# XMICRO-BP8.net
KiCad netlist of a schematic drawn in EAGLE
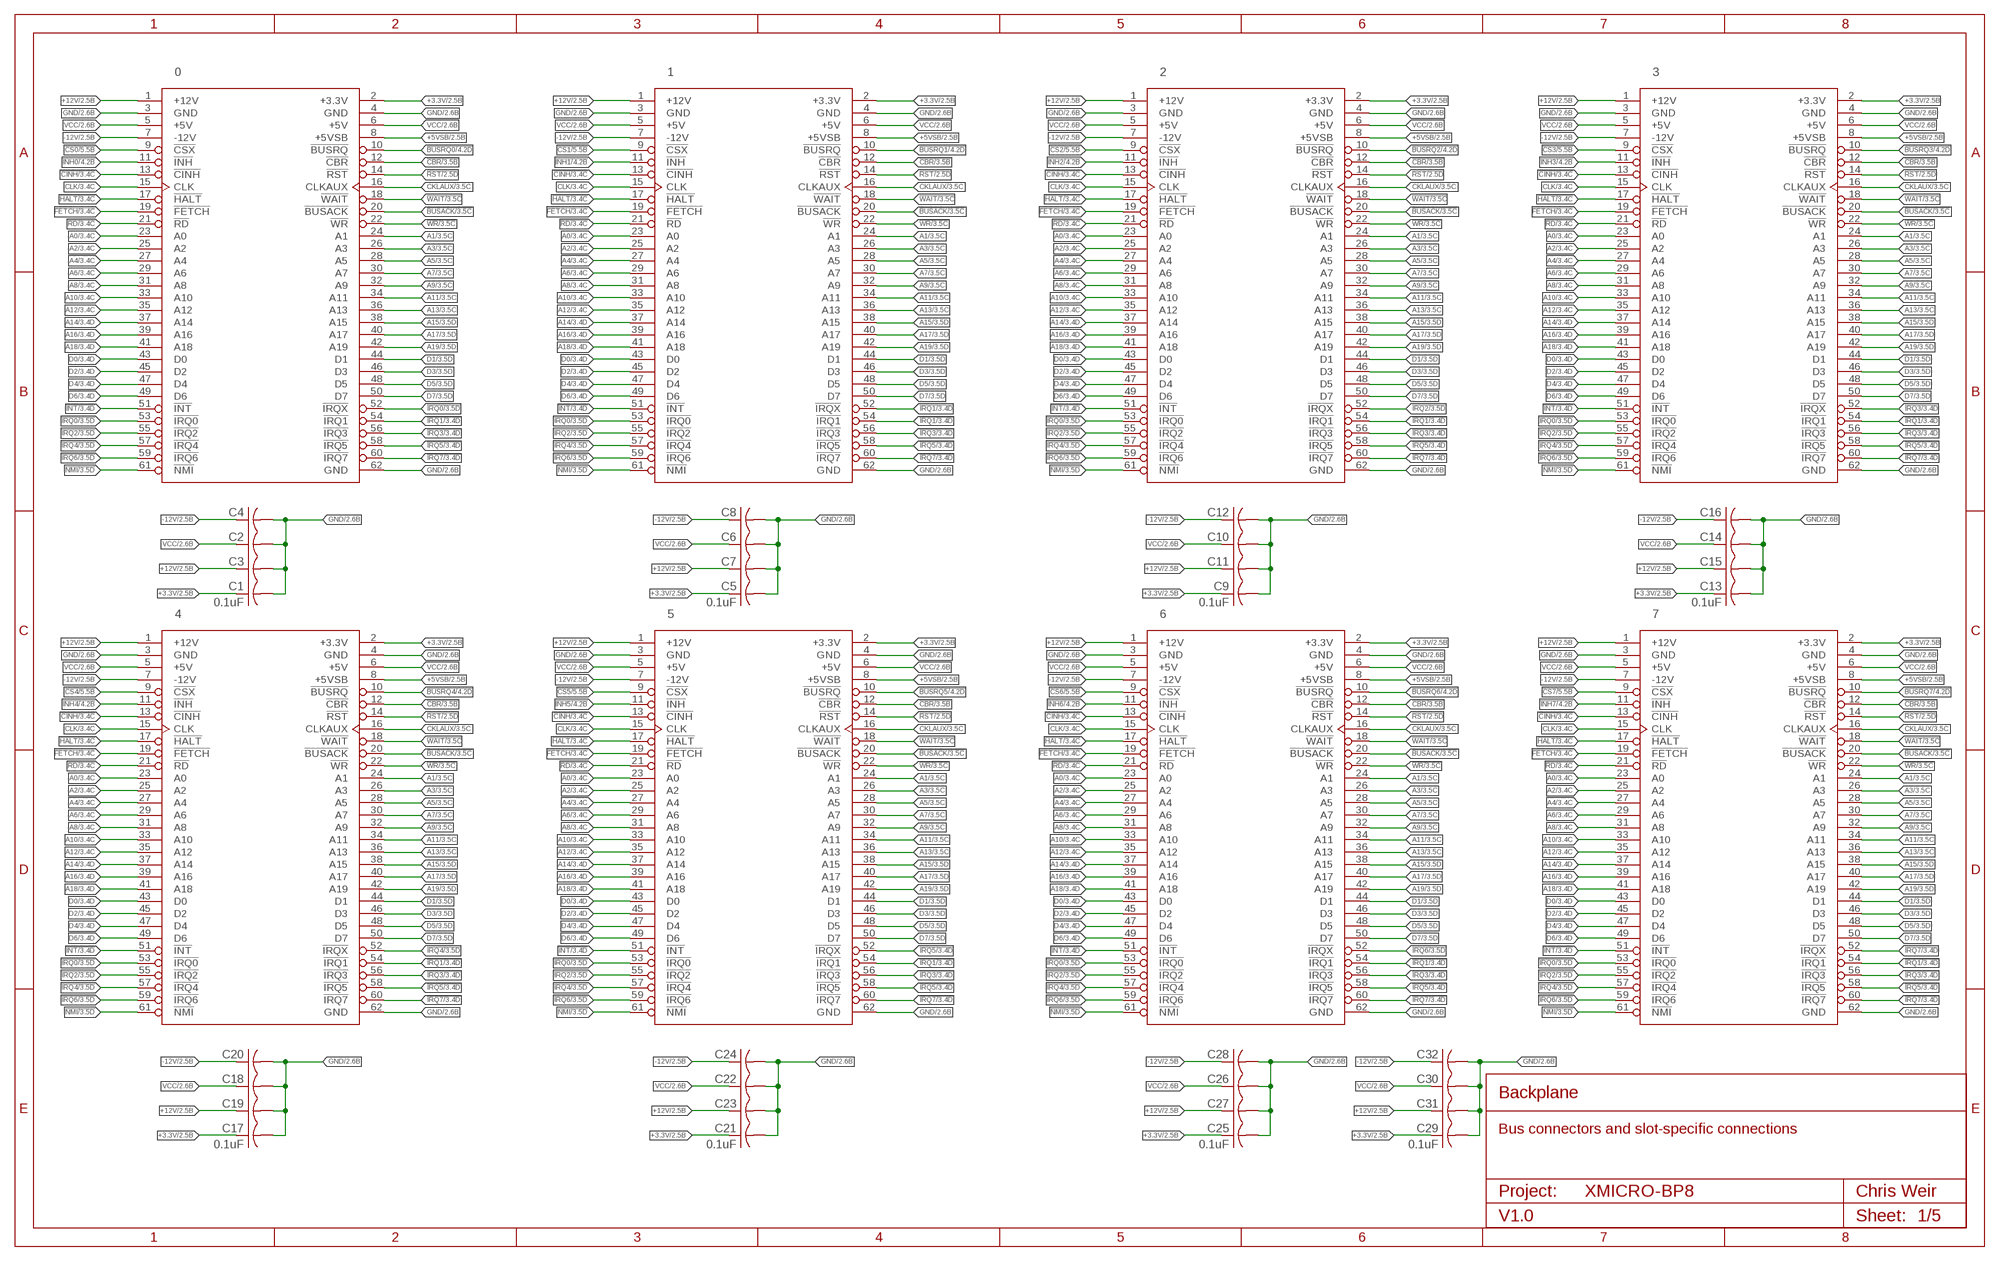
[diagram p0: schematic, sheet 1]
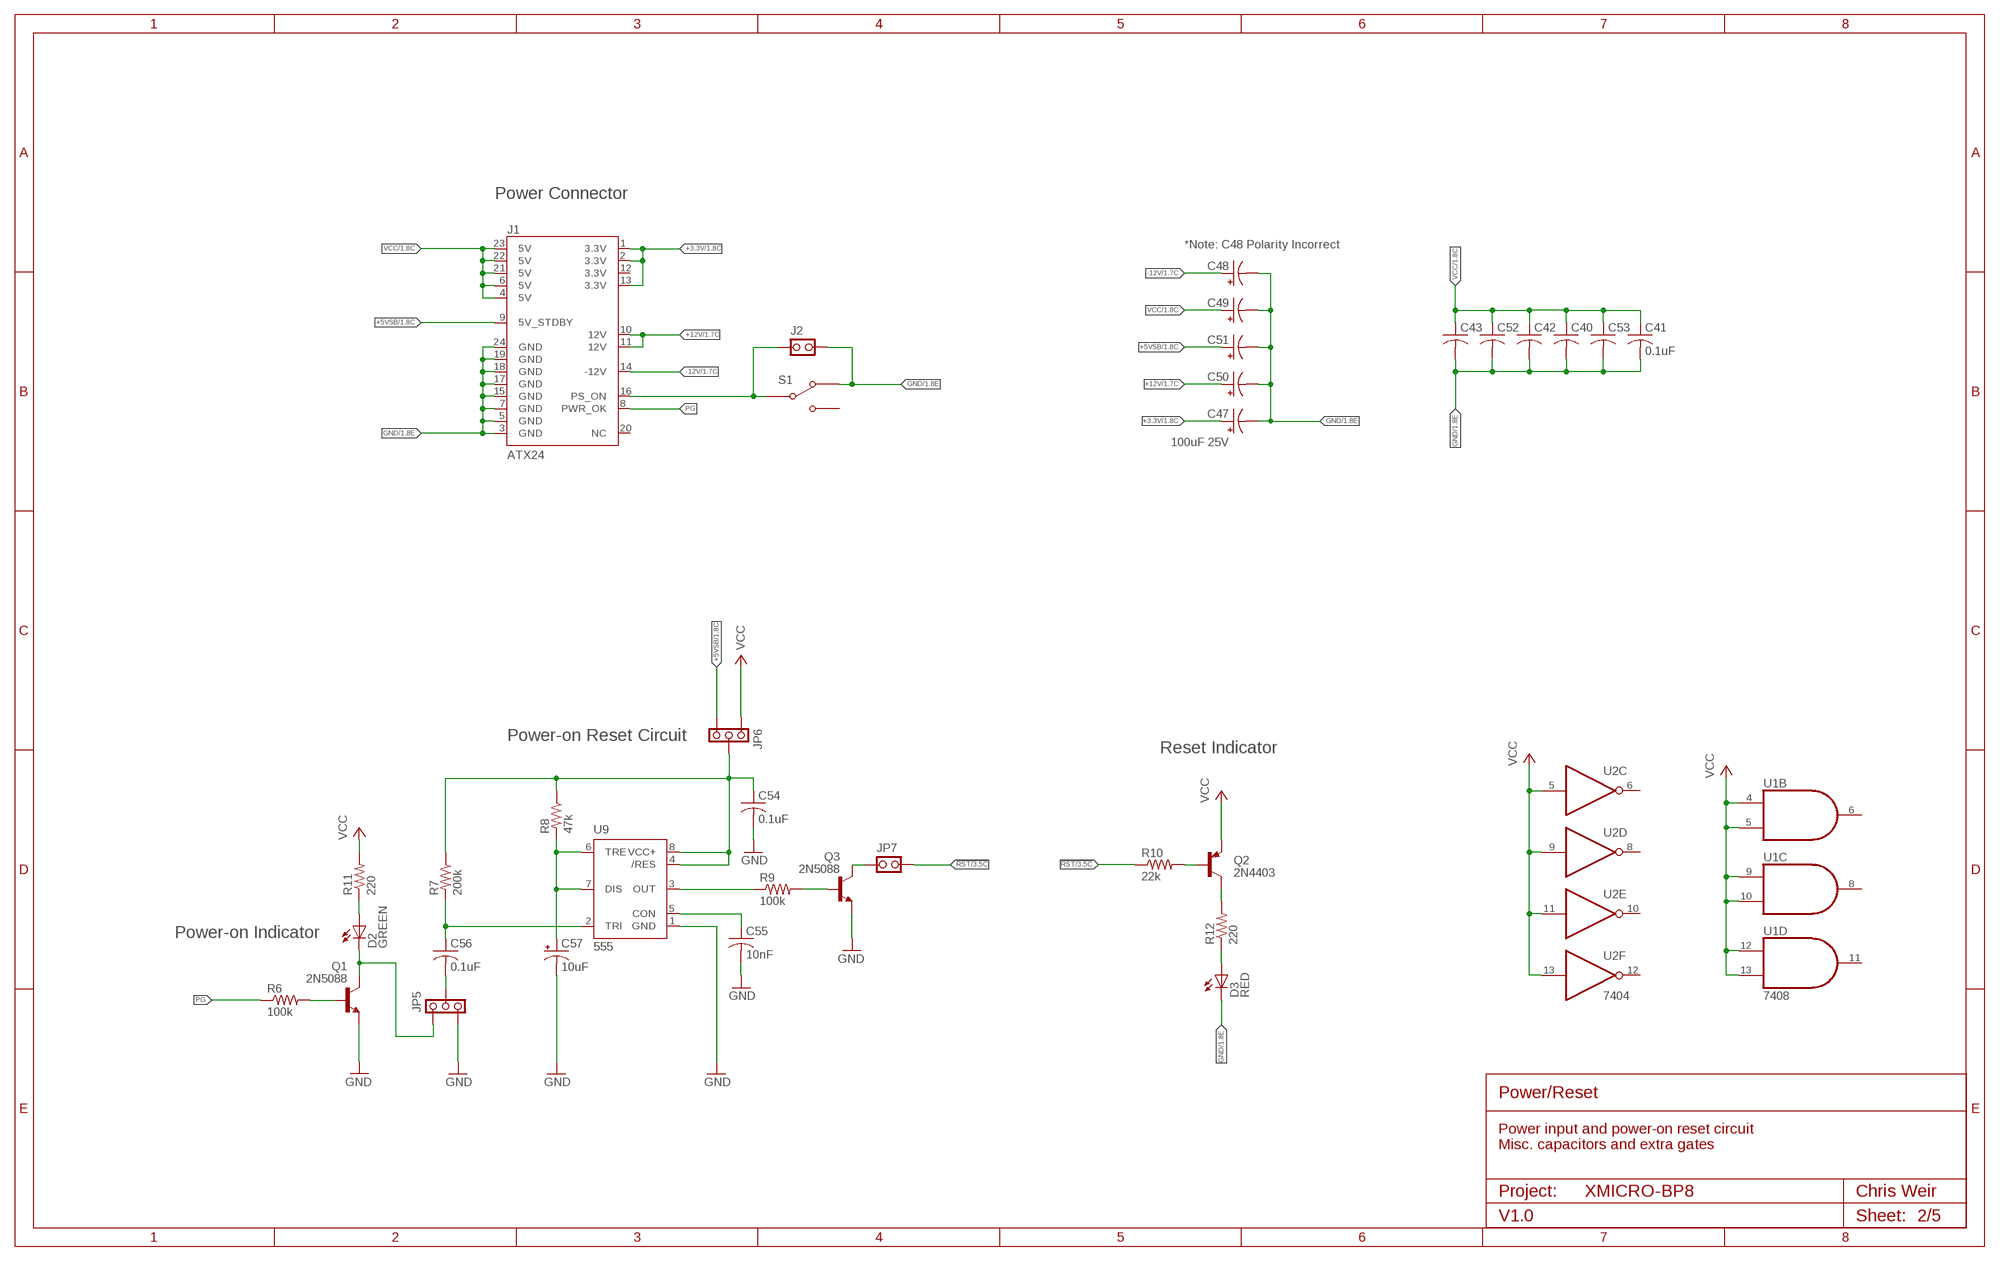
[diagram p1: schematic, sheet 2]
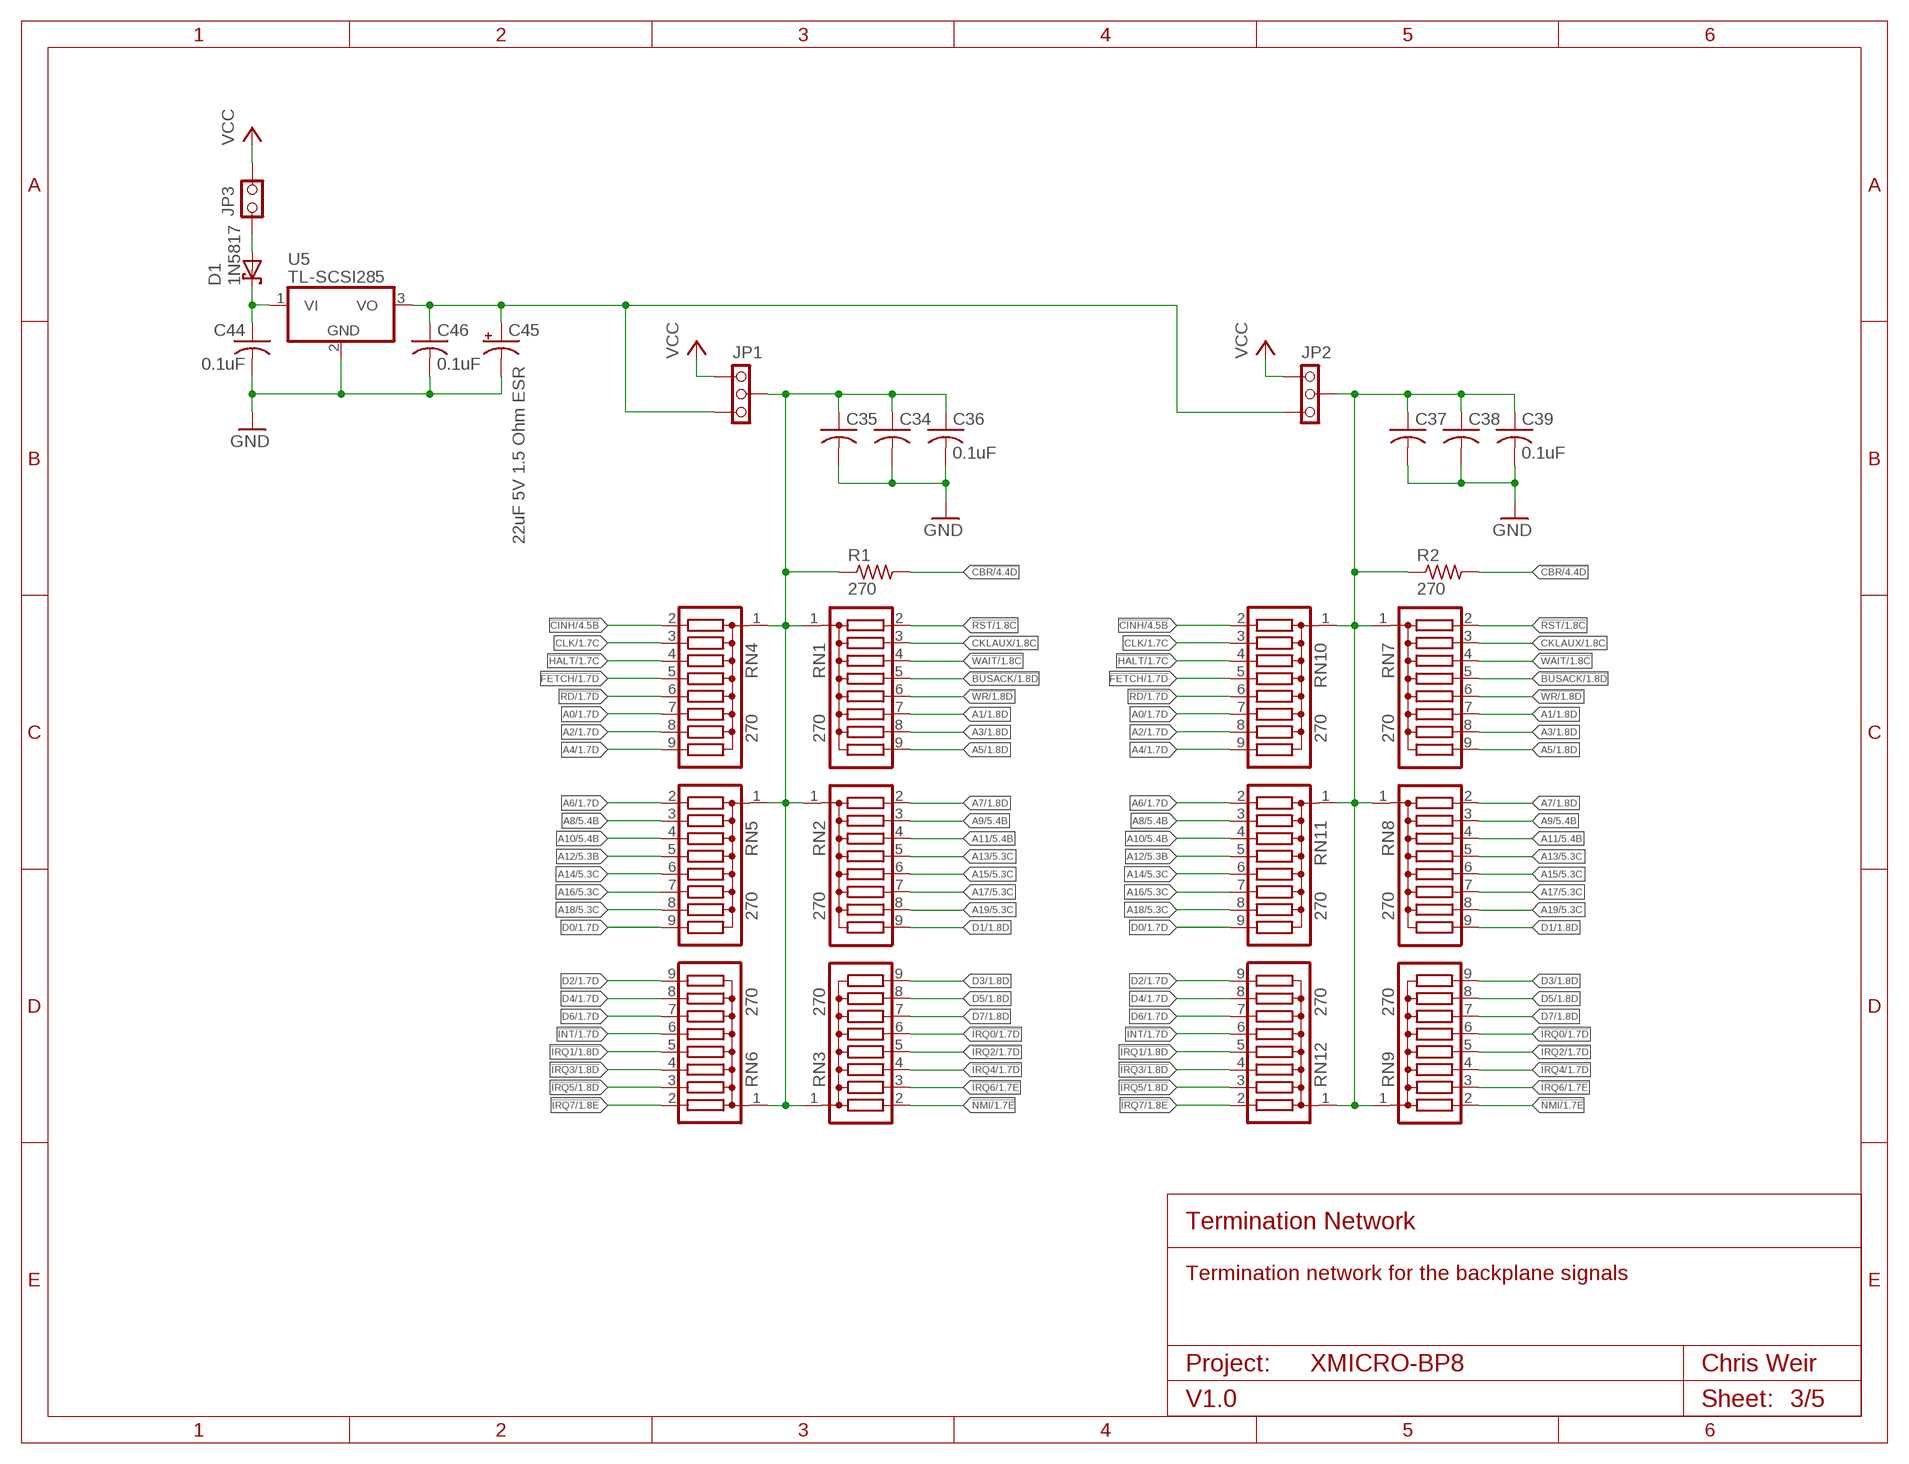
[diagram p2: schematic, sheet 3]
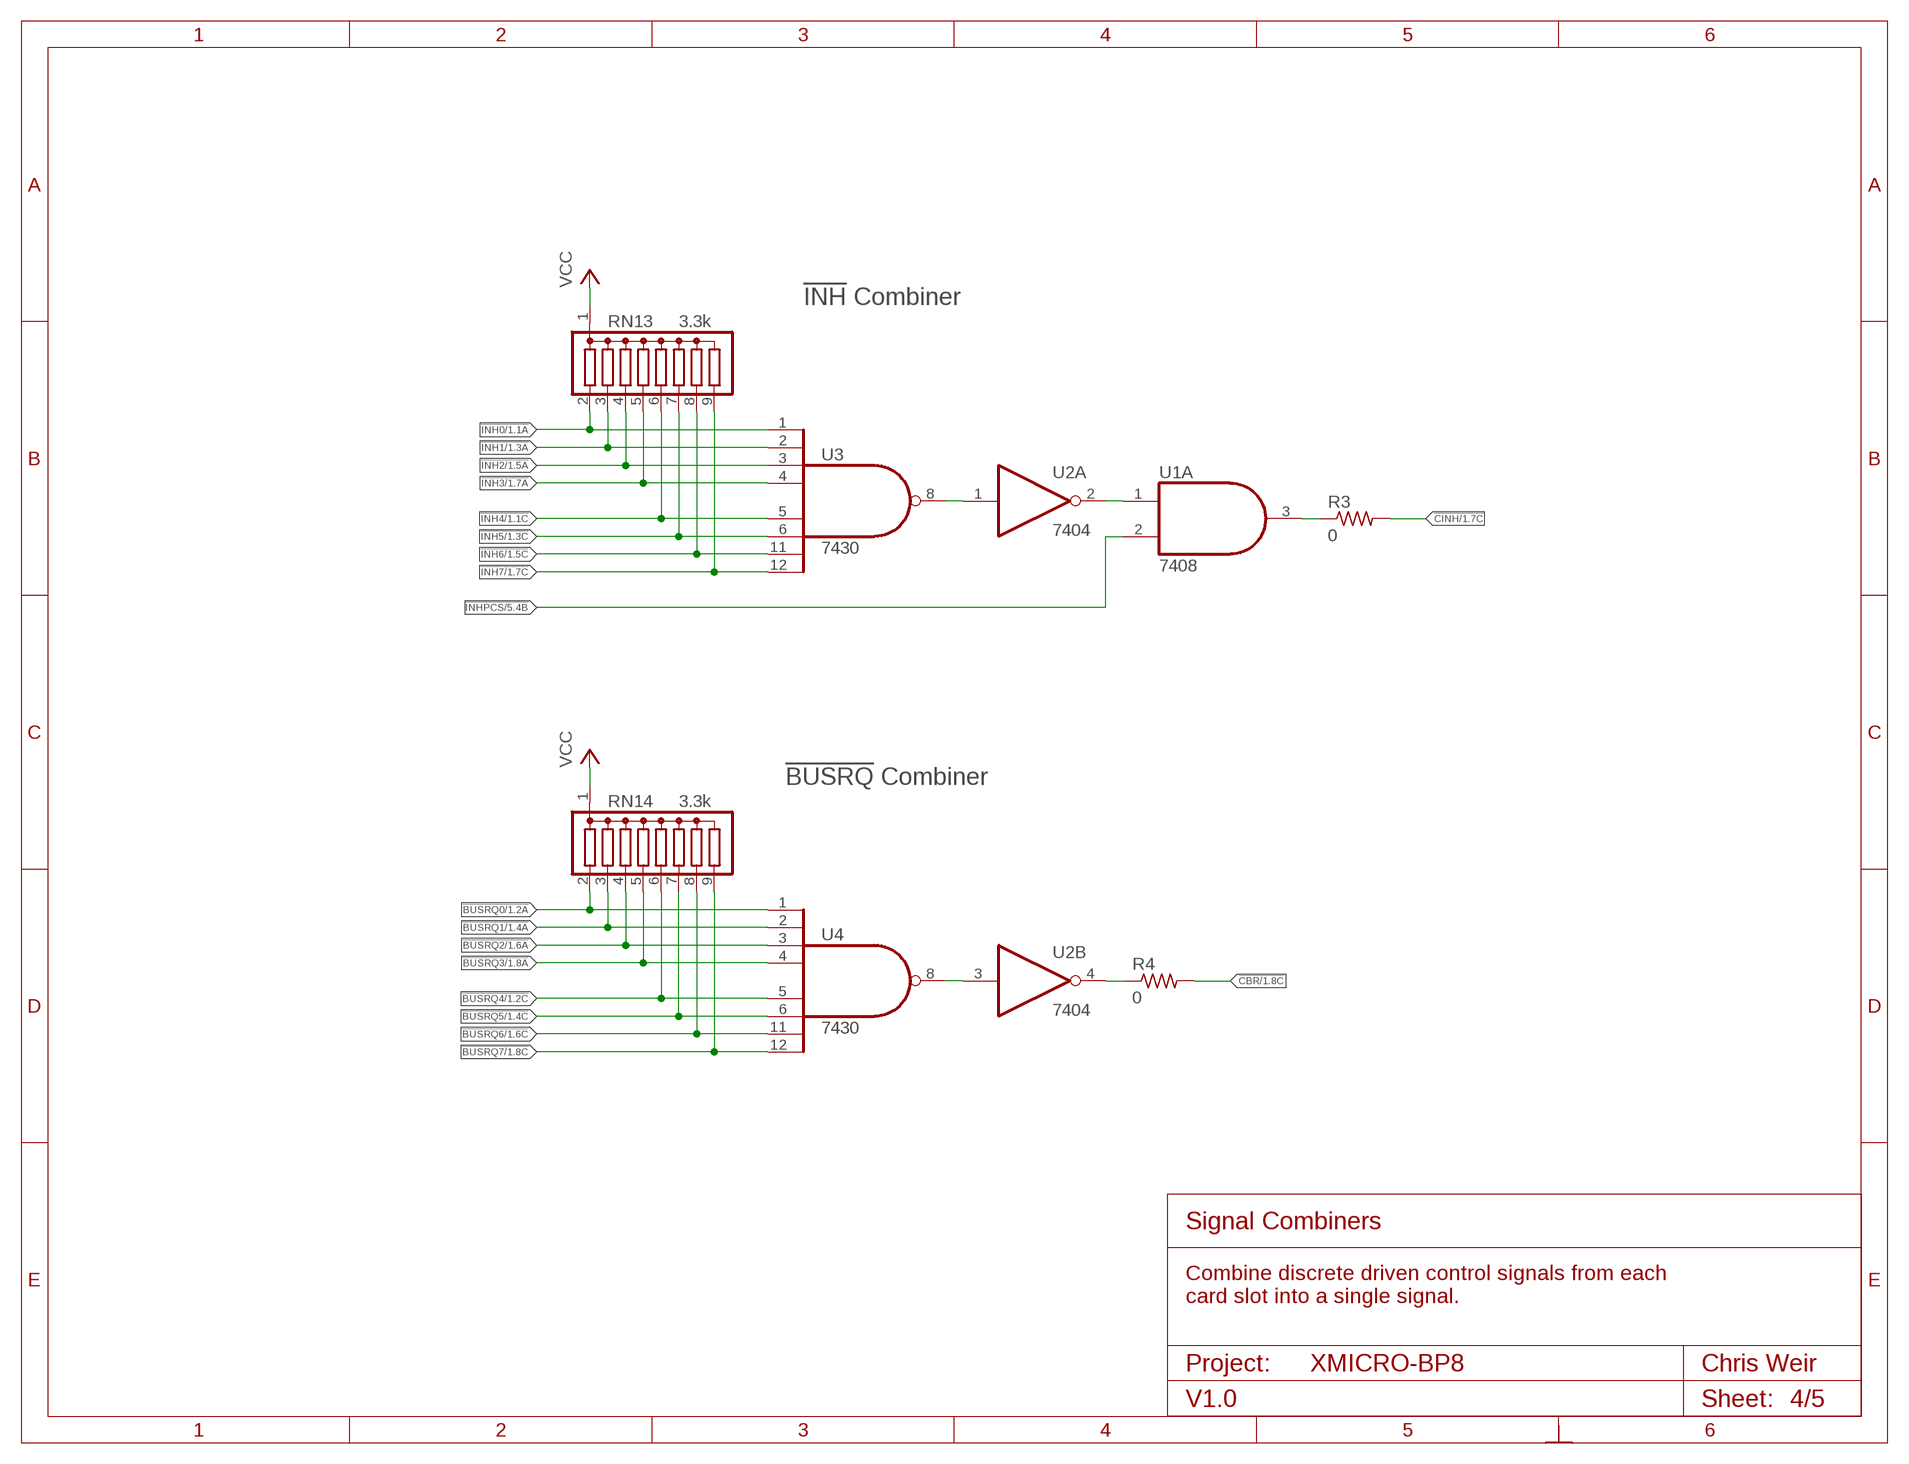
[diagram p3: schematic, sheet 4]
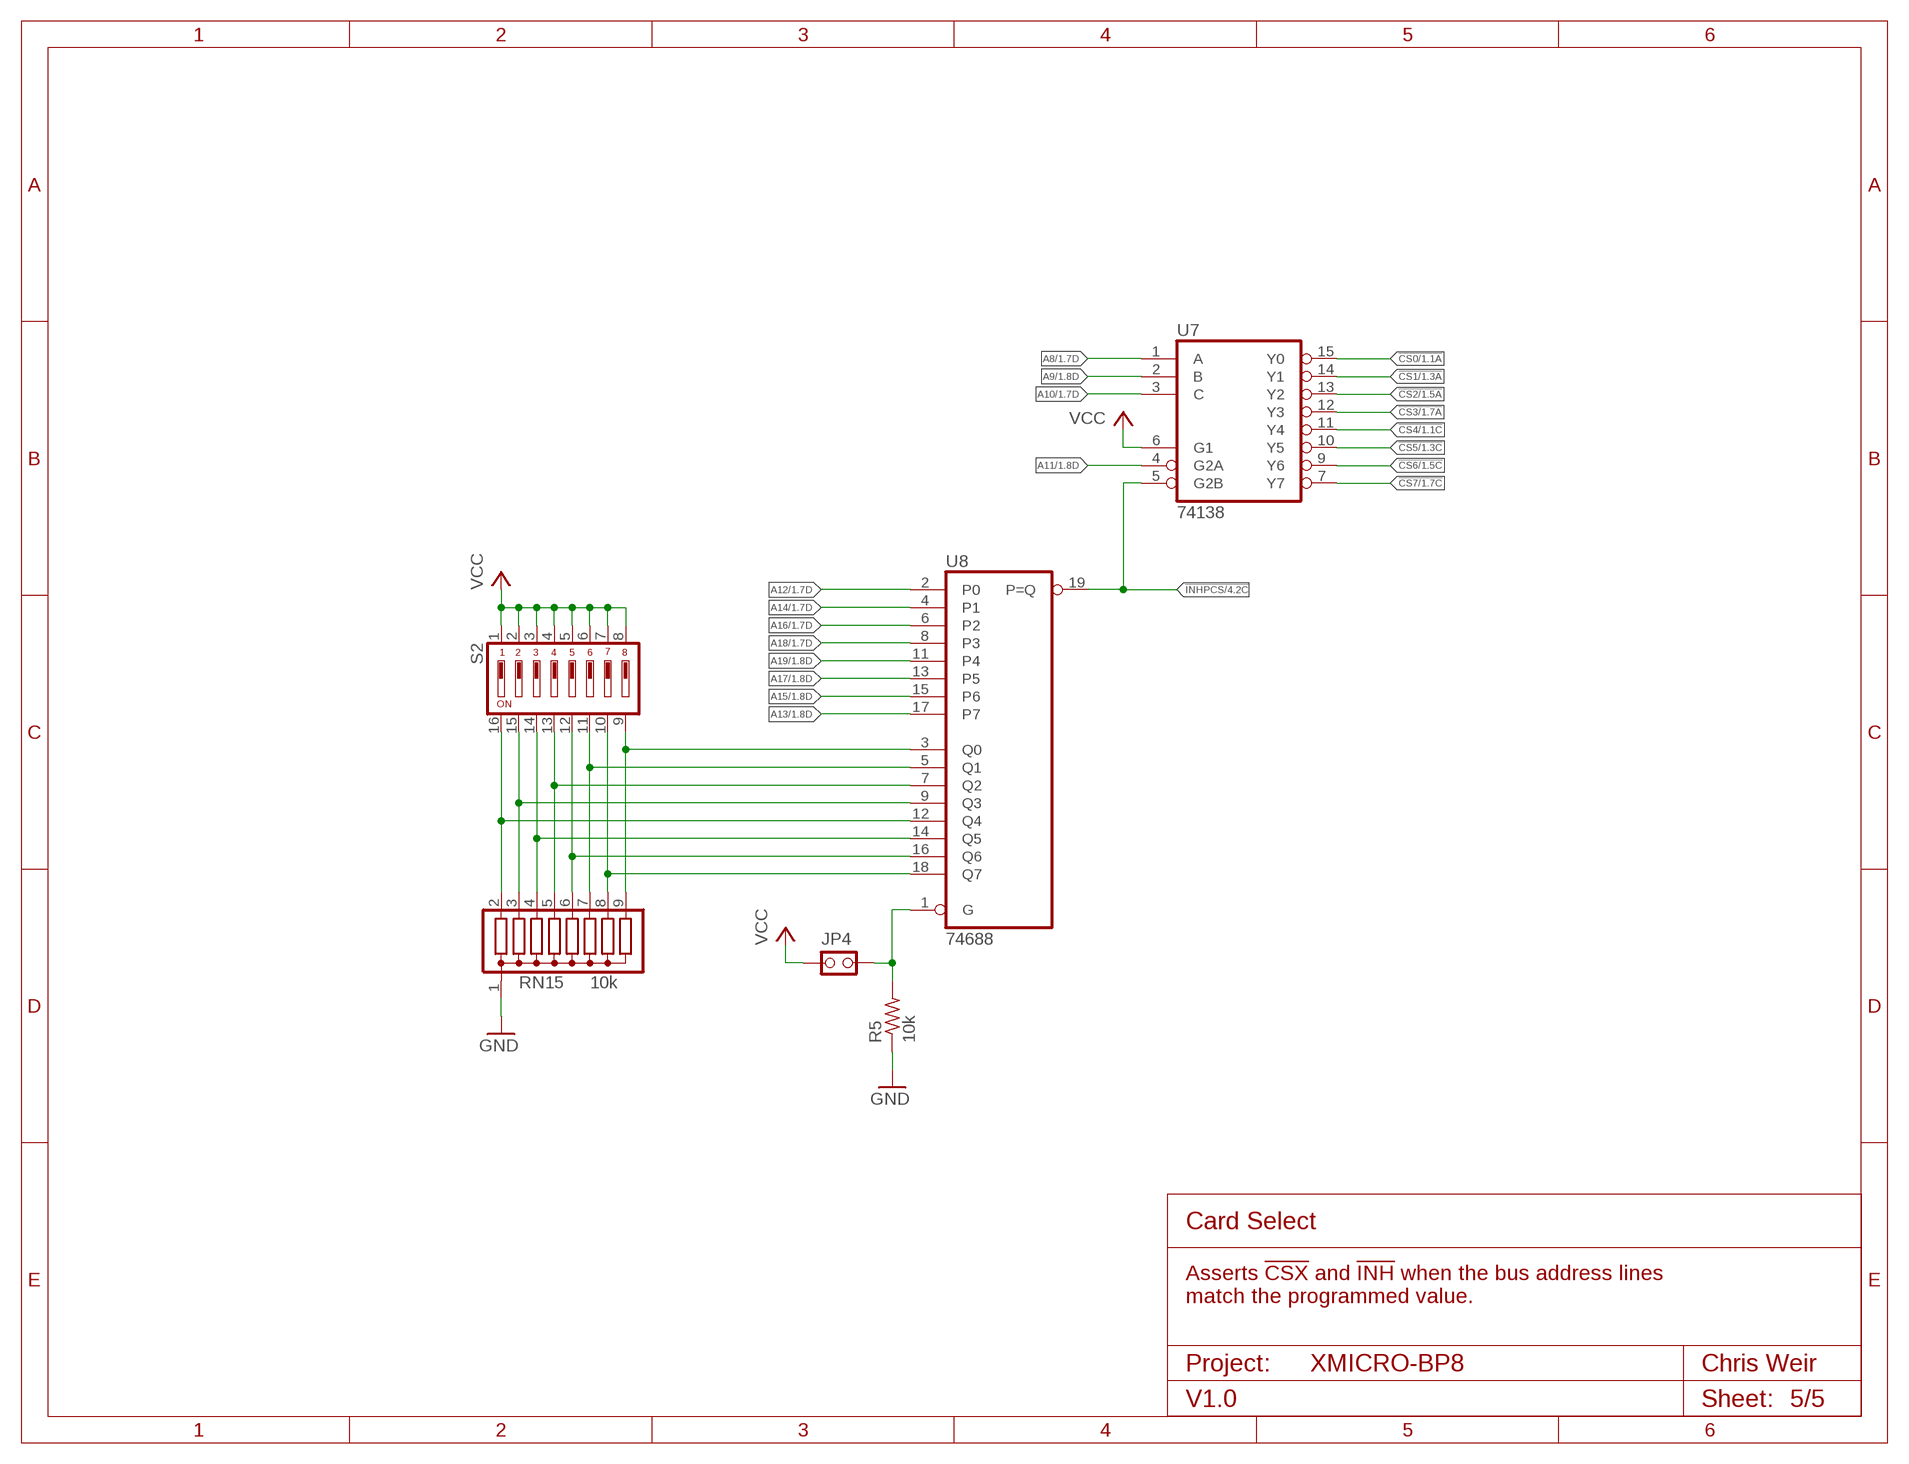
[diagram p4: schematic, sheet 5]

(export (version "E")
  (design (tool "Eeschema 10.0.6"))
  (components
    (comp (ref "C34")
      (value "0.1uF")
      (footprint "eagle-import:C025-024X044")
      (libsource (lib "eagle-import") (part "C-US025-024X044"))
    )
    (comp (ref "C35")
      (value "0.1uF")
      (footprint "eagle-import:C025-024X044")
      (libsource (lib "eagle-import") (part "C-US025-024X044"))
    )
    (comp (ref "C36")
      (value "0.1uF")
      (footprint "eagle-import:C025-024X044")
      (libsource (lib "eagle-import") (part "C-US025-024X044"))
    )
    (comp (ref "C37")
      (value "0.1uF")
      (footprint "eagle-import:C025-024X044")
      (libsource (lib "eagle-import") (part "C-US025-024X044"))
    )
    (comp (ref "C38")
      (value "0.1uF")
      (footprint "eagle-import:C025-024X044")
      (libsource (lib "eagle-import") (part "C-US025-024X044"))
    )
    (comp (ref "C39")
      (value "0.1uF")
      (footprint "eagle-import:C025-024X044")
      (libsource (lib "eagle-import") (part "C-US025-024X044"))
    )
    (comp (ref "C44")
      (value "0.1uF")
      (footprint "eagle-import:C025-024X044")
      (libsource (lib "eagle-import") (part "C-US025-024X044"))
    )
    (comp (ref "C45")
      (value "22uF 5V 1.5 Ohm ESR")
      (footprint "eagle-import:E2,5-7")
      (libsource (lib "eagle-import") (part "CPOL-USE2.5-7"))
    )
    (comp (ref "C46")
      (value "0.1uF")
      (footprint "eagle-import:C050-024X044")
      (libsource (lib "eagle-import") (part "C-US050-024X044"))
    )
    (comp (ref "D1")
      (value "1N5817")
      (footprint "eagle-import:DO41-7.6")
      (libsource (lib "eagle-import") (part "1N5817-B"))
    )
    (comp (ref "JP1")
      (value "PINHD1X3THRU")
      (footprint "eagle-import:1X03")
      (libsource (lib "eagle-import") (part "PINHD1X3THRU"))
    )
    (comp (ref "JP2")
      (value "PINHD1X3THRU")
      (footprint "eagle-import:1X03")
      (libsource (lib "eagle-import") (part "PINHD1X3THRU"))
    )
    (comp (ref "JP3")
      (value "PINHD-1X2THRU")
      (footprint "eagle-import:1X02")
      (libsource (lib "eagle-import") (part "PINHD-1X2THRU"))
    )
    (comp (ref "R1")
      (value "270")
      (footprint "eagle-import:0207_10")
      (libsource (lib "eagle-import") (part "R-US_0207/10"))
    )
    (comp (ref "R2")
      (value "270")
      (footprint "eagle-import:0207_10")
      (libsource (lib "eagle-import") (part "R-US_0207/10"))
    )
    (comp (ref "RN1")
      (value "270")
      (footprint "eagle-import:SIL9")
      (fields (field (name "OC_FARNELL") "unknown") (field (name "OC_NEWARK") "unknown"))
      (libsource (lib "eagle-import") (part "G08R"))
    )
    (comp (ref "RN2")
      (value "270")
      (footprint "eagle-import:SIL9")
      (fields (field (name "OC_FARNELL") "unknown") (field (name "OC_NEWARK") "unknown"))
      (libsource (lib "eagle-import") (part "G08R"))
    )
    (comp (ref "RN3")
      (value "270")
      (footprint "eagle-import:SIL9")
      (fields (field (name "OC_FARNELL") "unknown") (field (name "OC_NEWARK") "unknown"))
      (libsource (lib "eagle-import") (part "G08R"))
    )
    (comp (ref "RN4")
      (value "270")
      (footprint "eagle-import:SIL9")
      (fields (field (name "OC_FARNELL") "unknown") (field (name "OC_NEWARK") "unknown"))
      (libsource (lib "eagle-import") (part "G08R"))
    )
    (comp (ref "RN5")
      (value "270")
      (footprint "eagle-import:SIL9")
      (fields (field (name "OC_FARNELL") "unknown") (field (name "OC_NEWARK") "unknown"))
      (libsource (lib "eagle-import") (part "G08R"))
    )
    (comp (ref "RN6")
      (value "270")
      (footprint "eagle-import:SIL9")
      (fields (field (name "OC_FARNELL") "unknown") (field (name "OC_NEWARK") "unknown"))
      (libsource (lib "eagle-import") (part "G08R"))
    )
    (comp (ref "RN7")
      (value "270")
      (footprint "eagle-import:SIL9")
      (fields (field (name "OC_FARNELL") "unknown") (field (name "OC_NEWARK") "unknown"))
      (libsource (lib "eagle-import") (part "G08R"))
    )
    (comp (ref "RN8")
      (value "270")
      (footprint "eagle-import:SIL9")
      (fields (field (name "OC_FARNELL") "unknown") (field (name "OC_NEWARK") "unknown"))
      (libsource (lib "eagle-import") (part "G08R"))
    )
    (comp (ref "RN9")
      (value "270")
      (footprint "eagle-import:SIL9")
      (fields (field (name "OC_FARNELL") "unknown") (field (name "OC_NEWARK") "unknown"))
      (libsource (lib "eagle-import") (part "G08R"))
    )
    (comp (ref "RN10")
      (value "270")
      (footprint "eagle-import:SIL9")
      (fields (field (name "OC_FARNELL") "unknown") (field (name "OC_NEWARK") "unknown"))
      (libsource (lib "eagle-import") (part "G08R"))
    )
    (comp (ref "RN11")
      (value "270")
      (footprint "eagle-import:SIL9")
      (fields (field (name "OC_FARNELL") "unknown") (field (name "OC_NEWARK") "unknown"))
      (libsource (lib "eagle-import") (part "G08R"))
    )
    (comp (ref "RN12")
      (value "270")
      (footprint "eagle-import:SIL9")
      (fields (field (name "OC_FARNELL") "unknown") (field (name "OC_NEWARK") "unknown"))
      (libsource (lib "eagle-import") (part "G08R"))
    )
    (comp (ref "U5")
      (value "TL-SCSI285")
      (footprint "eagle-import:TO220H")
      (libsource (lib "eagle-import") (part "TL-SCSI285-TO220H"))
    )
    (comp (ref "C40")
      (value "0.1uF")
      (footprint "eagle-import:C025-024X044")
      (libsource (lib "eagle-import") (part "C-US025-024X044"))
    )
    (comp (ref "C41")
      (value "0.1uF")
      (footprint "eagle-import:C025-024X044")
      (libsource (lib "eagle-import") (part "C-US025-024X044"))
    )
    (comp (ref "C42")
      (value "0.1uF")
      (footprint "eagle-import:C025-024X044")
      (libsource (lib "eagle-import") (part "C-US025-024X044"))
    )
    (comp (ref "C43")
      (value "0.1uF")
      (footprint "eagle-import:C025-024X044")
      (libsource (lib "eagle-import") (part "C-US025-024X044"))
    )
    (comp (ref "C47")
      (value "100uF 25V")
      (footprint "eagle-import:C-10-5")
      (libsource (lib "eagle-import") (part "CPOL-US-10-5"))
    )
    (comp (ref "C48")
      (value "220uF 10V")
      (footprint "eagle-import:C-10-5")
      (libsource (lib "eagle-import") (part "CPOL-US-10-5"))
    )
    (comp (ref "C49")
      (value "220uF 10V")
      (footprint "eagle-import:C-10-5")
      (libsource (lib "eagle-import") (part "CPOL-US-10-5"))
    )
    (comp (ref "C50")
      (value "100uF 25V")
      (footprint "eagle-import:C-10-5")
      (libsource (lib "eagle-import") (part "CPOL-US-10-5"))
    )
    (comp (ref "C51")
      (value "220uF 10V")
      (footprint "eagle-import:C-10-5")
      (libsource (lib "eagle-import") (part "CPOL-US-10-5"))
    )
    (comp (ref "C52")
      (value "0.1uF")
      (footprint "eagle-import:C025-024X044")
      (libsource (lib "eagle-import") (part "C-US025-024X044"))
    )
    (comp (ref "C53")
      (value "0.1uF")
      (footprint "eagle-import:C025-024X044")
      (libsource (lib "eagle-import") (part "C-US025-024X044"))
    )
    (comp (ref "C54")
      (value "0.1uF")
      (footprint "eagle-import:C025-024X044")
      (libsource (lib "eagle-import") (part "C-US025-024X044"))
    )
    (comp (ref "C55")
      (value "10nF")
      (footprint "eagle-import:C025-024X044")
      (libsource (lib "eagle-import") (part "C-US025-024X044"))
    )
    (comp (ref "C56")
      (value "0.1uF")
      (footprint "eagle-import:C025-024X044")
      (libsource (lib "eagle-import") (part "C-US025-024X044"))
    )
    (comp (ref "C57")
      (value "10uF")
      (footprint "eagle-import:E2,5-7")
      (libsource (lib "eagle-import") (part "CPOL-USE2.5-7"))
    )
    (comp (ref "D2")
      (value "GREEN")
      (footprint "eagle-import:LED5MM")
      (libsource (lib "eagle-import") (part "LED5MM"))
    )
    (comp (ref "D3")
      (value "RED")
      (footprint "eagle-import:LED5MM")
      (libsource (lib "eagle-import") (part "LED5MM"))
    )
    (comp (ref "J1")
      (value "ATX24")
      (footprint "eagle-import:ATX24")
      (libsource (lib "eagle-import") (part "ATX24"))
    )
    (comp (ref "J2")
      (value "PINHD-1X2THRU")
      (footprint "eagle-import:1X02")
      (libsource (lib "eagle-import") (part "PINHD-1X2THRU"))
    )
    (comp (ref "JP5")
      (value "PINHD1X3THRU")
      (footprint "eagle-import:1X03")
      (libsource (lib "eagle-import") (part "PINHD1X3THRU"))
    )
    (comp (ref "JP6")
      (value "PINHD1X3THRU")
      (footprint "eagle-import:1X03")
      (libsource (lib "eagle-import") (part "PINHD1X3THRU"))
    )
    (comp (ref "JP7")
      (value "PINHD-1X2THRU")
      (footprint "eagle-import:1X02")
      (libsource (lib "eagle-import") (part "PINHD-1X2THRU"))
    )
    (comp (ref "Q1")
      (value "2N5088")
      (footprint "eagle-import:TO92")
      (libsource (lib "eagle-import") (part "TRANSISTOR-NPN-2N5088"))
    )
    (comp (ref "Q2")
      (value "2N4403")
      (footprint "eagle-import:TO92")
      (libsource (lib "eagle-import") (part "TRANSISTOR-PNP-2N4403"))
    )
    (comp (ref "Q3")
      (value "2N5088")
      (footprint "eagle-import:TO92")
      (libsource (lib "eagle-import") (part "TRANSISTOR-NPN-2N5088"))
    )
    (comp (ref "R6")
      (value "100k")
      (footprint "eagle-import:0207_10")
      (libsource (lib "eagle-import") (part "R-US_0207/10"))
    )
    (comp (ref "R7")
      (value "200k")
      (footprint "eagle-import:0207_10")
      (libsource (lib "eagle-import") (part "R-US_0207/10"))
    )
    (comp (ref "R8")
      (value "47k")
      (footprint "eagle-import:0207_10")
      (libsource (lib "eagle-import") (part "R-US_0207/10"))
    )
    (comp (ref "R9")
      (value "100k")
      (footprint "eagle-import:0207_10")
      (libsource (lib "eagle-import") (part "R-US_0207/10"))
    )
    (comp (ref "R10")
      (value "22k")
      (footprint "eagle-import:0207_10")
      (libsource (lib "eagle-import") (part "R-US_0207/10"))
    )
    (comp (ref "R11")
      (value "220")
      (footprint "eagle-import:0207_10")
      (libsource (lib "eagle-import") (part "R-US_0207/10"))
    )
    (comp (ref "R12")
      (value "220")
      (footprint "eagle-import:0207_10")
      (libsource (lib "eagle-import") (part "R-US_0207/10"))
    )
    (comp (ref "S1")
      (value "SPDTT411013")
      (footprint "eagle-import:T411013")
      (libsource (lib "eagle-import") (part "SPDTT411013"))
    )
    (comp (ref "U1")
      (value "7408")
      (footprint "eagle-import:DIL14")
      (libsource (lib "eagle-import") (part "7408NLS"))
    )
    (comp (ref "U2")
      (value "7404")
      (footprint "eagle-import:DIL14")
      (libsource (lib "eagle-import") (part "7404NLS"))
    )
    (comp (ref "U9")
      (value "555")
      (footprint "eagle-import:DIL-08")
      (fields (field (name "MF") "Arrow Electronics") (field (name "MPN") "NE555N"))
      (libsource (lib "eagle-import") (part "NE555"))
    )
    (comp (ref "R3")
      (value "0")
      (footprint "eagle-import:0207_10")
      (libsource (lib "eagle-import") (part "R-US_0207/10"))
    )
    (comp (ref "R4")
      (value "0")
      (footprint "eagle-import:0207_10")
      (libsource (lib "eagle-import") (part "R-US_0207/10"))
    )
    (comp (ref "RN13")
      (value "3.3k")
      (footprint "eagle-import:SIL9")
      (fields (field (name "OC_FARNELL") "unknown") (field (name "OC_NEWARK") "unknown"))
      (libsource (lib "eagle-import") (part "G08R"))
    )
    (comp (ref "RN14")
      (value "3.3k")
      (footprint "eagle-import:SIL9")
      (fields (field (name "OC_FARNELL") "unknown") (field (name "OC_NEWARK") "unknown"))
      (libsource (lib "eagle-import") (part "G08R"))
    )
    (comp (ref "U3")
      (value "7430")
      (footprint "eagle-import:DIL14")
      (libsource (lib "eagle-import") (part "7430NLS"))
    )
    (comp (ref "U4")
      (value "7430")
      (footprint "eagle-import:DIL14")
      (libsource (lib "eagle-import") (part "7430NLS"))
    )
    (comp (ref "JP4")
      (value "PINHD-1X2THRU")
      (footprint "eagle-import:1X02")
      (libsource (lib "eagle-import") (part "PINHD-1X2THRU"))
    )
    (comp (ref "R5")
      (value "10k")
      (footprint "eagle-import:0207_10")
      (libsource (lib "eagle-import") (part "R-US_0207/10"))
    )
    (comp (ref "RN15")
      (value "10k")
      (footprint "eagle-import:SIL9")
      (fields (field (name "OC_FARNELL") "unknown") (field (name "OC_NEWARK") "unknown"))
      (libsource (lib "eagle-import") (part "G08R"))
    )
    (comp (ref "S2")
      (value "SW-DIP08")
      (footprint "eagle-import:SW-DIP8")
      (libsource (lib "eagle-import") (part "SW-DIP08"))
    )
    (comp (ref "U7")
      (value "74138")
      (footprint "eagle-import:DIL16")
      (libsource (lib "eagle-import") (part "74138NLS"))
    )
    (comp (ref "U8")
      (value "74688")
      (footprint "eagle-import:DIL20")
      (libsource (lib "eagle-import") (part "74688NLS"))
    )
    (comp (ref "0")
      (value "XMICRO-BUS-PHYSICAL-EDGE62F")
      (footprint "eagle-import:EDGE62F")
      (libsource (lib "eagle-import") (part "XMICRO-BUS-PHYSICAL-EDGE62F"))
    )
    (comp (ref "1")
      (value "XMICRO-BUS-PHYSICAL-EDGE62F")
      (footprint "eagle-import:EDGE62F")
      (libsource (lib "eagle-import") (part "XMICRO-BUS-PHYSICAL-EDGE62F"))
    )
    (comp (ref "2")
      (value "XMICRO-BUS-PHYSICAL-EDGE62F")
      (footprint "eagle-import:EDGE62F")
      (libsource (lib "eagle-import") (part "XMICRO-BUS-PHYSICAL-EDGE62F"))
    )
    (comp (ref "3")
      (value "XMICRO-BUS-PHYSICAL-EDGE62F")
      (footprint "eagle-import:EDGE62F")
      (libsource (lib "eagle-import") (part "XMICRO-BUS-PHYSICAL-EDGE62F"))
    )
    (comp (ref "4")
      (value "XMICRO-BUS-PHYSICAL-EDGE62F")
      (footprint "eagle-import:EDGE62F")
      (libsource (lib "eagle-import") (part "XMICRO-BUS-PHYSICAL-EDGE62F"))
    )
    (comp (ref "5")
      (value "XMICRO-BUS-PHYSICAL-EDGE62F")
      (footprint "eagle-import:EDGE62F")
      (libsource (lib "eagle-import") (part "XMICRO-BUS-PHYSICAL-EDGE62F"))
    )
    (comp (ref "6")
      (value "XMICRO-BUS-PHYSICAL-EDGE62F")
      (footprint "eagle-import:EDGE62F")
      (libsource (lib "eagle-import") (part "XMICRO-BUS-PHYSICAL-EDGE62F"))
    )
    (comp (ref "7")
      (value "XMICRO-BUS-PHYSICAL-EDGE62F")
      (footprint "eagle-import:EDGE62F")
      (libsource (lib "eagle-import") (part "XMICRO-BUS-PHYSICAL-EDGE62F"))
    )
    (comp (ref "C1")
      (value "0.1uF")
      (footprint "eagle-import:C025-024X044")
      (libsource (lib "eagle-import") (part "C-US025-024X044"))
    )
    (comp (ref "C2")
      (value "0.1uF")
      (footprint "eagle-import:C025-024X044")
      (libsource (lib "eagle-import") (part "C-US025-024X044"))
    )
    (comp (ref "C3")
      (value "0.1uF")
      (footprint "eagle-import:C025-024X044")
      (libsource (lib "eagle-import") (part "C-US025-024X044"))
    )
    (comp (ref "C4")
      (value "0.1uF")
      (footprint "eagle-import:C050-024X044")
      (libsource (lib "eagle-import") (part "C-US050-024X044"))
    )
    (comp (ref "C5")
      (value "0.1uF")
      (footprint "eagle-import:C025-024X044")
      (libsource (lib "eagle-import") (part "C-US025-024X044"))
    )
    (comp (ref "C6")
      (value "0.1uF")
      (footprint "eagle-import:C025-024X044")
      (libsource (lib "eagle-import") (part "C-US025-024X044"))
    )
    (comp (ref "C7")
      (value "0.1uF")
      (footprint "eagle-import:C025-024X044")
      (libsource (lib "eagle-import") (part "C-US025-024X044"))
    )
    (comp (ref "C8")
      (value "0.1uF")
      (footprint "eagle-import:C050-024X044")
      (libsource (lib "eagle-import") (part "C-US050-024X044"))
    )
    (comp (ref "C9")
      (value "0.1uF")
      (footprint "eagle-import:C025-024X044")
      (libsource (lib "eagle-import") (part "C-US025-024X044"))
    )
    (comp (ref "C10")
      (value "0.1uF")
      (footprint "eagle-import:C025-024X044")
      (libsource (lib "eagle-import") (part "C-US025-024X044"))
    )
    (comp (ref "C11")
      (value "0.1uF")
      (footprint "eagle-import:C025-024X044")
      (libsource (lib "eagle-import") (part "C-US025-024X044"))
    )
    (comp (ref "C12")
      (value "0.1uF")
      (footprint "eagle-import:C050-024X044")
      (libsource (lib "eagle-import") (part "C-US050-024X044"))
    )
    (comp (ref "C13")
      (value "0.1uF")
      (footprint "eagle-import:C025-024X044")
      (libsource (lib "eagle-import") (part "C-US025-024X044"))
    )
    (comp (ref "C14")
      (value "0.1uF")
      (footprint "eagle-import:C025-024X044")
      (libsource (lib "eagle-import") (part "C-US025-024X044"))
    )
    (comp (ref "C15")
      (value "0.1uF")
      (footprint "eagle-import:C025-024X044")
      (libsource (lib "eagle-import") (part "C-US025-024X044"))
    )
    (comp (ref "C16")
      (value "0.1uF")
      (footprint "eagle-import:C050-024X044")
      (libsource (lib "eagle-import") (part "C-US050-024X044"))
    )
    (comp (ref "C17")
      (value "0.1uF")
      (footprint "eagle-import:C025-024X044")
      (libsource (lib "eagle-import") (part "C-US025-024X044"))
    )
    (comp (ref "C18")
      (value "0.1uF")
      (footprint "eagle-import:C025-024X044")
      (libsource (lib "eagle-import") (part "C-US025-024X044"))
    )
    (comp (ref "C19")
      (value "0.1uF")
      (footprint "eagle-import:C025-024X044")
      (libsource (lib "eagle-import") (part "C-US025-024X044"))
    )
    (comp (ref "C20")
      (value "0.1uF")
      (footprint "eagle-import:C050-024X044")
      (libsource (lib "eagle-import") (part "C-US050-024X044"))
    )
    (comp (ref "C21")
      (value "0.1uF")
      (footprint "eagle-import:C025-024X044")
      (libsource (lib "eagle-import") (part "C-US025-024X044"))
    )
    (comp (ref "C22")
      (value "0.1uF")
      (footprint "eagle-import:C025-024X044")
      (libsource (lib "eagle-import") (part "C-US025-024X044"))
    )
    (comp (ref "C23")
      (value "0.1uF")
      (footprint "eagle-import:C025-024X044")
      (libsource (lib "eagle-import") (part "C-US025-024X044"))
    )
    (comp (ref "C24")
      (value "0.1uF")
      (footprint "eagle-import:C050-024X044")
      (libsource (lib "eagle-import") (part "C-US050-024X044"))
    )
    (comp (ref "C25")
      (value "0.1uF")
      (footprint "eagle-import:C025-024X044")
      (libsource (lib "eagle-import") (part "C-US025-024X044"))
    )
    (comp (ref "C26")
      (value "0.1uF")
      (footprint "eagle-import:C025-024X044")
      (libsource (lib "eagle-import") (part "C-US025-024X044"))
    )
    (comp (ref "C27")
      (value "0.1uF")
      (footprint "eagle-import:C025-024X044")
      (libsource (lib "eagle-import") (part "C-US025-024X044"))
    )
    (comp (ref "C28")
      (value "0.1uF")
      (footprint "eagle-import:C050-024X044")
      (libsource (lib "eagle-import") (part "C-US050-024X044"))
    )
    (comp (ref "C29")
      (value "0.1uF")
      (footprint "eagle-import:C025-024X044")
      (libsource (lib "eagle-import") (part "C-US025-024X044"))
    )
    (comp (ref "C30")
      (value "0.1uF")
      (footprint "eagle-import:C025-024X044")
      (libsource (lib "eagle-import") (part "C-US025-024X044"))
    )
    (comp (ref "C31")
      (value "0.1uF")
      (footprint "eagle-import:C025-024X044")
      (libsource (lib "eagle-import") (part "C-US025-024X044"))
    )
    (comp (ref "C32")
      (value "0.1uF")
      (footprint "eagle-import:C025-024X044")
      (libsource (lib "eagle-import") (part "C-US025-024X044"))
    )
  )
  (nets
    (net (code "1") (name "+3.3V") (class "Default")
      (node (ref "0") (pin "2") (pinfunction "+3.3V_2") (pintype "bidirectional"))
      (node (ref "1") (pin "2") (pinfunction "+3.3V_2") (pintype "bidirectional"))
      (node (ref "2") (pin "2") (pinfunction "+3.3V_2") (pintype "bidirectional"))
      (node (ref "3") (pin "2") (pinfunction "+3.3V_2") (pintype "bidirectional"))
      (node (ref "4") (pin "2") (pinfunction "+3.3V_2") (pintype "bidirectional"))
      (node (ref "5") (pin "2") (pinfunction "+3.3V_2") (pintype "bidirectional"))
      (node (ref "6") (pin "2") (pinfunction "+3.3V_2") (pintype "bidirectional"))
      (node (ref "7") (pin "2") (pinfunction "+3.3V_2") (pintype "bidirectional"))
      (node (ref "C1") (pin "1") (pinfunction "1_1") (pintype "passive"))
      (node (ref "C13") (pin "1") (pinfunction "1_1") (pintype "passive"))
      (node (ref "C17") (pin "1") (pinfunction "1_1") (pintype "passive"))
      (node (ref "C21") (pin "1") (pinfunction "1_1") (pintype "passive"))
      (node (ref "C25") (pin "1") (pinfunction "1_1") (pintype "passive"))
      (node (ref "C29") (pin "1") (pinfunction "1_1") (pintype "passive"))
      (node (ref "C47") (pin "+") (pinfunction "+_+") (pintype "passive"))
      (node (ref "C5") (pin "1") (pinfunction "1_1") (pintype "passive"))
      (node (ref "C9") (pin "1") (pinfunction "1_1") (pintype "passive"))
      (node (ref "J1") (pin "1") (pinfunction "3.3V_1") (pintype "bidirectional"))
      (node (ref "J1") (pin "13") (pinfunction "3.3V_13") (pintype "bidirectional"))
      (node (ref "J1") (pin "2") (pinfunction "3.3V_2") (pintype "bidirectional"))
    )
    (net (code "2") (name "+5VSB") (class "Default")
      (node (ref "0") (pin "8") (pinfunction "+5VSB_8") (pintype "bidirectional"))
      (node (ref "1") (pin "8") (pinfunction "+5VSB_8") (pintype "bidirectional"))
      (node (ref "2") (pin "8") (pinfunction "+5VSB_8") (pintype "bidirectional"))
      (node (ref "3") (pin "8") (pinfunction "+5VSB_8") (pintype "bidirectional"))
      (node (ref "4") (pin "8") (pinfunction "+5VSB_8") (pintype "bidirectional"))
      (node (ref "5") (pin "8") (pinfunction "+5VSB_8") (pintype "bidirectional"))
      (node (ref "6") (pin "8") (pinfunction "+5VSB_8") (pintype "bidirectional"))
      (node (ref "7") (pin "8") (pinfunction "+5VSB_8") (pintype "bidirectional"))
      (node (ref "C51") (pin "+") (pinfunction "+_+") (pintype "passive"))
      (node (ref "J1") (pin "9") (pinfunction "5V_STDBY_9") (pintype "bidirectional"))
      (node (ref "JP6") (pin "3") (pinfunction "3_3") (pintype "passive"))
    )
    (net (code "3") (name "+12V") (class "Default")
      (node (ref "0") (pin "1") (pinfunction "+12V_1") (pintype "bidirectional"))
      (node (ref "1") (pin "1") (pinfunction "+12V_1") (pintype "bidirectional"))
      (node (ref "2") (pin "1") (pinfunction "+12V_1") (pintype "bidirectional"))
      (node (ref "3") (pin "1") (pinfunction "+12V_1") (pintype "bidirectional"))
      (node (ref "4") (pin "1") (pinfunction "+12V_1") (pintype "bidirectional"))
      (node (ref "5") (pin "1") (pinfunction "+12V_1") (pintype "bidirectional"))
      (node (ref "6") (pin "1") (pinfunction "+12V_1") (pintype "bidirectional"))
      (node (ref "7") (pin "1") (pinfunction "+12V_1") (pintype "bidirectional"))
      (node (ref "C11") (pin "1") (pinfunction "1_1") (pintype "passive"))
      (node (ref "C15") (pin "1") (pinfunction "1_1") (pintype "passive"))
      (node (ref "C19") (pin "1") (pinfunction "1_1") (pintype "passive"))
      (node (ref "C23") (pin "1") (pinfunction "1_1") (pintype "passive"))
      (node (ref "C27") (pin "1") (pinfunction "1_1") (pintype "passive"))
      (node (ref "C3") (pin "1") (pinfunction "1_1") (pintype "passive"))
      (node (ref "C31") (pin "1") (pinfunction "1_1") (pintype "passive"))
      (node (ref "C50") (pin "+") (pinfunction "+_+") (pintype "passive"))
      (node (ref "C7") (pin "1") (pinfunction "1_1") (pintype "passive"))
      (node (ref "J1") (pin "10") (pinfunction "12V_10") (pintype "bidirectional"))
      (node (ref "J1") (pin "11") (pinfunction "12V_11") (pintype "bidirectional"))
    )
    (net (code "4") (name "-12V") (class "Default")
      (node (ref "0") (pin "7") (pinfunction "-12V_7") (pintype "bidirectional"))
      (node (ref "1") (pin "7") (pinfunction "-12V_7") (pintype "bidirectional"))
      (node (ref "2") (pin "7") (pinfunction "-12V_7") (pintype "bidirectional"))
      (node (ref "3") (pin "7") (pinfunction "-12V_7") (pintype "bidirectional"))
      (node (ref "4") (pin "7") (pinfunction "-12V_7") (pintype "bidirectional"))
      (node (ref "5") (pin "7") (pinfunction "-12V_7") (pintype "bidirectional"))
      (node (ref "6") (pin "7") (pinfunction "-12V_7") (pintype "bidirectional"))
      (node (ref "7") (pin "7") (pinfunction "-12V_7") (pintype "bidirectional"))
      (node (ref "C12") (pin "1") (pinfunction "1_1") (pintype "passive"))
      (node (ref "C16") (pin "1") (pinfunction "1_1") (pintype "passive"))
      (node (ref "C20") (pin "1") (pinfunction "1_1") (pintype "passive"))
      (node (ref "C24") (pin "1") (pinfunction "1_1") (pintype "passive"))
      (node (ref "C28") (pin "1") (pinfunction "1_1") (pintype "passive"))
      (node (ref "C32") (pin "1") (pinfunction "1_1") (pintype "passive"))
      (node (ref "C4") (pin "1") (pinfunction "1_1") (pintype "passive"))
      (node (ref "C48") (pin "+") (pinfunction "+_+") (pintype "passive"))
      (node (ref "C8") (pin "1") (pinfunction "1_1") (pintype "passive"))
      (node (ref "J1") (pin "14") (pinfunction "-12V_14") (pintype "bidirectional"))
    )
    (net (code "5") (name "A0") (class "Default")
      (node (ref "0") (pin "23") (pinfunction "A0_23") (pintype "bidirectional"))
      (node (ref "1") (pin "23") (pinfunction "A0_23") (pintype "bidirectional"))
      (node (ref "2") (pin "23") (pinfunction "A0_23") (pintype "bidirectional"))
      (node (ref "3") (pin "23") (pinfunction "A0_23") (pintype "bidirectional"))
      (node (ref "4") (pin "23") (pinfunction "A0_23") (pintype "bidirectional"))
      (node (ref "5") (pin "23") (pinfunction "A0_23") (pintype "bidirectional"))
      (node (ref "6") (pin "23") (pinfunction "A0_23") (pintype "bidirectional"))
      (node (ref "7") (pin "23") (pinfunction "A0_23") (pintype "bidirectional"))
      (node (ref "RN10") (pin "7") (pinfunction "7_7") (pintype "passive"))
      (node (ref "RN4") (pin "7") (pinfunction "7_7") (pintype "passive"))
    )
    (net (code "6") (name "A1") (class "Default")
      (node (ref "0") (pin "24") (pinfunction "A1_24") (pintype "bidirectional"))
      (node (ref "1") (pin "24") (pinfunction "A1_24") (pintype "bidirectional"))
      (node (ref "2") (pin "24") (pinfunction "A1_24") (pintype "bidirectional"))
      (node (ref "3") (pin "24") (pinfunction "A1_24") (pintype "bidirectional"))
      (node (ref "4") (pin "24") (pinfunction "A1_24") (pintype "bidirectional"))
      (node (ref "5") (pin "24") (pinfunction "A1_24") (pintype "bidirectional"))
      (node (ref "6") (pin "24") (pinfunction "A1_24") (pintype "bidirectional"))
      (node (ref "7") (pin "24") (pinfunction "A1_24") (pintype "bidirectional"))
      (node (ref "RN1") (pin "7") (pinfunction "7_7") (pintype "passive"))
      (node (ref "RN7") (pin "7") (pinfunction "7_7") (pintype "passive"))
    )
    (net (code "7") (name "A2") (class "Default")
      (node (ref "0") (pin "25") (pinfunction "A2_25") (pintype "bidirectional"))
      (node (ref "1") (pin "25") (pinfunction "A2_25") (pintype "bidirectional"))
      (node (ref "2") (pin "25") (pinfunction "A2_25") (pintype "bidirectional"))
      (node (ref "3") (pin "25") (pinfunction "A2_25") (pintype "bidirectional"))
      (node (ref "4") (pin "25") (pinfunction "A2_25") (pintype "bidirectional"))
      (node (ref "5") (pin "25") (pinfunction "A2_25") (pintype "bidirectional"))
      (node (ref "6") (pin "25") (pinfunction "A2_25") (pintype "bidirectional"))
      (node (ref "7") (pin "25") (pinfunction "A2_25") (pintype "bidirectional"))
      (node (ref "RN10") (pin "8") (pinfunction "8_8") (pintype "passive"))
      (node (ref "RN4") (pin "8") (pinfunction "8_8") (pintype "passive"))
    )
    (net (code "8") (name "A3") (class "Default")
      (node (ref "0") (pin "26") (pinfunction "A3_26") (pintype "bidirectional"))
      (node (ref "1") (pin "26") (pinfunction "A3_26") (pintype "bidirectional"))
      (node (ref "2") (pin "26") (pinfunction "A3_26") (pintype "bidirectional"))
      (node (ref "3") (pin "26") (pinfunction "A3_26") (pintype "bidirectional"))
      (node (ref "4") (pin "26") (pinfunction "A3_26") (pintype "bidirectional"))
      (node (ref "5") (pin "26") (pinfunction "A3_26") (pintype "bidirectional"))
      (node (ref "6") (pin "26") (pinfunction "A3_26") (pintype "bidirectional"))
      (node (ref "7") (pin "26") (pinfunction "A3_26") (pintype "bidirectional"))
      (node (ref "RN1") (pin "8") (pinfunction "8_8") (pintype "passive"))
      (node (ref "RN7") (pin "8") (pinfunction "8_8") (pintype "passive"))
    )
    (net (code "9") (name "A4") (class "Default")
      (node (ref "0") (pin "27") (pinfunction "A4_27") (pintype "bidirectional"))
      (node (ref "1") (pin "27") (pinfunction "A4_27") (pintype "bidirectional"))
      (node (ref "2") (pin "27") (pinfunction "A4_27") (pintype "bidirectional"))
      (node (ref "3") (pin "27") (pinfunction "A4_27") (pintype "bidirectional"))
      (node (ref "4") (pin "27") (pinfunction "A4_27") (pintype "bidirectional"))
      (node (ref "5") (pin "27") (pinfunction "A4_27") (pintype "bidirectional"))
      (node (ref "6") (pin "27") (pinfunction "A4_27") (pintype "bidirectional"))
      (node (ref "7") (pin "27") (pinfunction "A4_27") (pintype "bidirectional"))
      (node (ref "RN10") (pin "9") (pinfunction "9_9") (pintype "passive"))
      (node (ref "RN4") (pin "9") (pinfunction "9_9") (pintype "passive"))
    )
    (net (code "10") (name "A5") (class "Default")
      (node (ref "0") (pin "28") (pinfunction "A5_28") (pintype "bidirectional"))
      (node (ref "1") (pin "28") (pinfunction "A5_28") (pintype "bidirectional"))
      (node (ref "2") (pin "28") (pinfunction "A5_28") (pintype "bidirectional"))
      (node (ref "3") (pin "28") (pinfunction "A5_28") (pintype "bidirectional"))
      (node (ref "4") (pin "28") (pinfunction "A5_28") (pintype "bidirectional"))
      (node (ref "5") (pin "28") (pinfunction "A5_28") (pintype "bidirectional"))
      (node (ref "6") (pin "28") (pinfunction "A5_28") (pintype "bidirectional"))
      (node (ref "7") (pin "28") (pinfunction "A5_28") (pintype "bidirectional"))
      (node (ref "RN1") (pin "9") (pinfunction "9_9") (pintype "passive"))
      (node (ref "RN7") (pin "9") (pinfunction "9_9") (pintype "passive"))
    )
    (net (code "11") (name "A6") (class "Default")
      (node (ref "0") (pin "29") (pinfunction "A6_29") (pintype "bidirectional"))
      (node (ref "1") (pin "29") (pinfunction "A6_29") (pintype "bidirectional"))
      (node (ref "2") (pin "29") (pinfunction "A6_29") (pintype "bidirectional"))
      (node (ref "3") (pin "29") (pinfunction "A6_29") (pintype "bidirectional"))
      (node (ref "4") (pin "29") (pinfunction "A6_29") (pintype "bidirectional"))
      (node (ref "5") (pin "29") (pinfunction "A6_29") (pintype "bidirectional"))
      (node (ref "6") (pin "29") (pinfunction "A6_29") (pintype "bidirectional"))
      (node (ref "7") (pin "29") (pinfunction "A6_29") (pintype "bidirectional"))
      (node (ref "RN11") (pin "2") (pinfunction "2_2") (pintype "passive"))
      (node (ref "RN5") (pin "2") (pinfunction "2_2") (pintype "passive"))
    )
    (net (code "12") (name "A7") (class "Default")
      (node (ref "0") (pin "30") (pinfunction "A7_30") (pintype "bidirectional"))
      (node (ref "1") (pin "30") (pinfunction "A7_30") (pintype "bidirectional"))
      (node (ref "2") (pin "30") (pinfunction "A7_30") (pintype "bidirectional"))
      (node (ref "3") (pin "30") (pinfunction "A7_30") (pintype "bidirectional"))
      (node (ref "4") (pin "30") (pinfunction "A7_30") (pintype "bidirectional"))
      (node (ref "5") (pin "30") (pinfunction "A7_30") (pintype "bidirectional"))
      (node (ref "6") (pin "30") (pinfunction "A7_30") (pintype "bidirectional"))
      (node (ref "7") (pin "30") (pinfunction "A7_30") (pintype "bidirectional"))
      (node (ref "RN2") (pin "2") (pinfunction "2_2") (pintype "passive"))
      (node (ref "RN8") (pin "2") (pinfunction "2_2") (pintype "passive"))
    )
    (net (code "13") (name "A8") (class "Default")
      (node (ref "0") (pin "31") (pinfunction "A8_31") (pintype "bidirectional"))
      (node (ref "1") (pin "31") (pinfunction "A8_31") (pintype "bidirectional"))
      (node (ref "2") (pin "31") (pinfunction "A8_31") (pintype "bidirectional"))
      (node (ref "3") (pin "31") (pinfunction "A8_31") (pintype "bidirectional"))
      (node (ref "4") (pin "31") (pinfunction "A8_31") (pintype "bidirectional"))
      (node (ref "5") (pin "31") (pinfunction "A8_31") (pintype "bidirectional"))
      (node (ref "6") (pin "31") (pinfunction "A8_31") (pintype "bidirectional"))
      (node (ref "7") (pin "31") (pinfunction "A8_31") (pintype "bidirectional"))
      (node (ref "RN11") (pin "3") (pinfunction "3_3") (pintype "passive"))
      (node (ref "RN5") (pin "3") (pinfunction "3_3") (pintype "passive"))
      (node (ref "U7") (pin "1") (pinfunction "A_1") (pintype "input"))
    )
    (net (code "14") (name "A9") (class "Default")
      (node (ref "0") (pin "32") (pinfunction "A9_32") (pintype "bidirectional"))
      (node (ref "1") (pin "32") (pinfunction "A9_32") (pintype "bidirectional"))
      (node (ref "2") (pin "32") (pinfunction "A9_32") (pintype "bidirectional"))
      (node (ref "3") (pin "32") (pinfunction "A9_32") (pintype "bidirectional"))
      (node (ref "4") (pin "32") (pinfunction "A9_32") (pintype "bidirectional"))
      (node (ref "5") (pin "32") (pinfunction "A9_32") (pintype "bidirectional"))
      (node (ref "6") (pin "32") (pinfunction "A9_32") (pintype "bidirectional"))
      (node (ref "7") (pin "32") (pinfunction "A9_32") (pintype "bidirectional"))
      (node (ref "RN2") (pin "3") (pinfunction "3_3") (pintype "passive"))
      (node (ref "RN8") (pin "3") (pinfunction "3_3") (pintype "passive"))
      (node (ref "U7") (pin "2") (pinfunction "B_2") (pintype "input"))
    )
    (net (code "15") (name "A10") (class "Default")
      (node (ref "0") (pin "33") (pinfunction "A10_33") (pintype "bidirectional"))
      (node (ref "1") (pin "33") (pinfunction "A10_33") (pintype "bidirectional"))
      (node (ref "2") (pin "33") (pinfunction "A10_33") (pintype "bidirectional"))
      (node (ref "3") (pin "33") (pinfunction "A10_33") (pintype "bidirectional"))
      (node (ref "4") (pin "33") (pinfunction "A10_33") (pintype "bidirectional"))
      (node (ref "5") (pin "33") (pinfunction "A10_33") (pintype "bidirectional"))
      (node (ref "6") (pin "33") (pinfunction "A10_33") (pintype "bidirectional"))
      (node (ref "7") (pin "33") (pinfunction "A10_33") (pintype "bidirectional"))
      (node (ref "RN11") (pin "4") (pinfunction "4_4") (pintype "passive"))
      (node (ref "RN5") (pin "4") (pinfunction "4_4") (pintype "passive"))
      (node (ref "U7") (pin "3") (pinfunction "C_3") (pintype "input"))
    )
    (net (code "16") (name "A11") (class "Default")
      (node (ref "0") (pin "34") (pinfunction "A11_34") (pintype "bidirectional"))
      (node (ref "1") (pin "34") (pinfunction "A11_34") (pintype "bidirectional"))
      (node (ref "2") (pin "34") (pinfunction "A11_34") (pintype "bidirectional"))
      (node (ref "3") (pin "34") (pinfunction "A11_34") (pintype "bidirectional"))
      (node (ref "4") (pin "34") (pinfunction "A11_34") (pintype "bidirectional"))
      (node (ref "5") (pin "34") (pinfunction "A11_34") (pintype "bidirectional"))
      (node (ref "6") (pin "34") (pinfunction "A11_34") (pintype "bidirectional"))
      (node (ref "7") (pin "34") (pinfunction "A11_34") (pintype "bidirectional"))
      (node (ref "RN2") (pin "4") (pinfunction "4_4") (pintype "passive"))
      (node (ref "RN8") (pin "4") (pinfunction "4_4") (pintype "passive"))
      (node (ref "U7") (pin "4") (pinfunction "G2A_4") (pintype "input"))
    )
    (net (code "17") (name "A12") (class "Default")
      (node (ref "0") (pin "35") (pinfunction "A12_35") (pintype "bidirectional"))
      (node (ref "1") (pin "35") (pinfunction "A12_35") (pintype "bidirectional"))
      (node (ref "2") (pin "35") (pinfunction "A12_35") (pintype "bidirectional"))
      (node (ref "3") (pin "35") (pinfunction "A12_35") (pintype "bidirectional"))
      (node (ref "4") (pin "35") (pinfunction "A12_35") (pintype "bidirectional"))
      (node (ref "5") (pin "35") (pinfunction "A12_35") (pintype "bidirectional"))
      (node (ref "6") (pin "35") (pinfunction "A12_35") (pintype "bidirectional"))
      (node (ref "7") (pin "35") (pinfunction "A12_35") (pintype "bidirectional"))
      (node (ref "RN11") (pin "5") (pinfunction "5_5") (pintype "passive"))
      (node (ref "RN5") (pin "5") (pinfunction "5_5") (pintype "passive"))
      (node (ref "U8") (pin "2") (pinfunction "P0_2") (pintype "input"))
    )
    (net (code "18") (name "A13") (class "Default")
      (node (ref "0") (pin "36") (pinfunction "A13_36") (pintype "bidirectional"))
      (node (ref "1") (pin "36") (pinfunction "A13_36") (pintype "bidirectional"))
      (node (ref "2") (pin "36") (pinfunction "A13_36") (pintype "bidirectional"))
      (node (ref "3") (pin "36") (pinfunction "A13_36") (pintype "bidirectional"))
      (node (ref "4") (pin "36") (pinfunction "A13_36") (pintype "bidirectional"))
      (node (ref "5") (pin "36") (pinfunction "A13_36") (pintype "bidirectional"))
      (node (ref "6") (pin "36") (pinfunction "A13_36") (pintype "bidirectional"))
      (node (ref "7") (pin "36") (pinfunction "A13_36") (pintype "bidirectional"))
      (node (ref "RN2") (pin "5") (pinfunction "5_5") (pintype "passive"))
      (node (ref "RN8") (pin "5") (pinfunction "5_5") (pintype "passive"))
      (node (ref "U8") (pin "17") (pinfunction "P7_17") (pintype "input"))
    )
    (net (code "19") (name "A14") (class "Default")
      (node (ref "0") (pin "37") (pinfunction "A14_37") (pintype "bidirectional"))
      (node (ref "1") (pin "37") (pinfunction "A14_37") (pintype "bidirectional"))
      (node (ref "2") (pin "37") (pinfunction "A14_37") (pintype "bidirectional"))
      (node (ref "3") (pin "37") (pinfunction "A14_37") (pintype "bidirectional"))
      (node (ref "4") (pin "37") (pinfunction "A14_37") (pintype "bidirectional"))
      (node (ref "5") (pin "37") (pinfunction "A14_37") (pintype "bidirectional"))
      (node (ref "6") (pin "37") (pinfunction "A14_37") (pintype "bidirectional"))
      (node (ref "7") (pin "37") (pinfunction "A14_37") (pintype "bidirectional"))
      (node (ref "RN11") (pin "6") (pinfunction "6_6") (pintype "passive"))
      (node (ref "RN5") (pin "6") (pinfunction "6_6") (pintype "passive"))
      (node (ref "U8") (pin "4") (pinfunction "P1_4") (pintype "input"))
    )
    (net (code "20") (name "A15") (class "Default")
      (node (ref "0") (pin "38") (pinfunction "A15_38") (pintype "bidirectional"))
      (node (ref "1") (pin "38") (pinfunction "A15_38") (pintype "bidirectional"))
      (node (ref "2") (pin "38") (pinfunction "A15_38") (pintype "bidirectional"))
      (node (ref "3") (pin "38") (pinfunction "A15_38") (pintype "bidirectional"))
      (node (ref "4") (pin "38") (pinfunction "A15_38") (pintype "bidirectional"))
      (node (ref "5") (pin "38") (pinfunction "A15_38") (pintype "bidirectional"))
      (node (ref "6") (pin "38") (pinfunction "A15_38") (pintype "bidirectional"))
      (node (ref "7") (pin "38") (pinfunction "A15_38") (pintype "bidirectional"))
      (node (ref "RN2") (pin "6") (pinfunction "6_6") (pintype "passive"))
      (node (ref "RN8") (pin "6") (pinfunction "6_6") (pintype "passive"))
      (node (ref "U8") (pin "15") (pinfunction "P6_15") (pintype "input"))
    )
    (net (code "21") (name "A16") (class "Default")
      (node (ref "0") (pin "39") (pinfunction "A16_39") (pintype "bidirectional"))
      (node (ref "1") (pin "39") (pinfunction "A16_39") (pintype "bidirectional"))
      (node (ref "2") (pin "39") (pinfunction "A16_39") (pintype "bidirectional"))
      (node (ref "3") (pin "39") (pinfunction "A16_39") (pintype "bidirectional"))
      (node (ref "4") (pin "39") (pinfunction "A16_39") (pintype "bidirectional"))
      (node (ref "5") (pin "39") (pinfunction "A16_39") (pintype "bidirectional"))
      (node (ref "6") (pin "39") (pinfunction "A16_39") (pintype "bidirectional"))
      (node (ref "7") (pin "39") (pinfunction "A16_39") (pintype "bidirectional"))
      (node (ref "RN11") (pin "7") (pinfunction "7_7") (pintype "passive"))
      (node (ref "RN5") (pin "7") (pinfunction "7_7") (pintype "passive"))
      (node (ref "U8") (pin "6") (pinfunction "P2_6") (pintype "input"))
    )
    (net (code "22") (name "A17") (class "Default")
      (node (ref "0") (pin "40") (pinfunction "A17_40") (pintype "bidirectional"))
      (node (ref "1") (pin "40") (pinfunction "A17_40") (pintype "bidirectional"))
      (node (ref "2") (pin "40") (pinfunction "A17_40") (pintype "bidirectional"))
      (node (ref "3") (pin "40") (pinfunction "A17_40") (pintype "bidirectional"))
      (node (ref "4") (pin "40") (pinfunction "A17_40") (pintype "bidirectional"))
      (node (ref "5") (pin "40") (pinfunction "A17_40") (pintype "bidirectional"))
      (node (ref "6") (pin "40") (pinfunction "A17_40") (pintype "bidirectional"))
      (node (ref "7") (pin "40") (pinfunction "A17_40") (pintype "bidirectional"))
      (node (ref "RN2") (pin "7") (pinfunction "7_7") (pintype "passive"))
      (node (ref "RN8") (pin "7") (pinfunction "7_7") (pintype "passive"))
      (node (ref "U8") (pin "13") (pinfunction "P5_13") (pintype "input"))
    )
    (net (code "23") (name "A18") (class "Default")
      (node (ref "0") (pin "41") (pinfunction "A18_41") (pintype "bidirectional"))
      (node (ref "1") (pin "41") (pinfunction "A18_41") (pintype "bidirectional"))
      (node (ref "2") (pin "41") (pinfunction "A18_41") (pintype "bidirectional"))
      (node (ref "3") (pin "41") (pinfunction "A18_41") (pintype "bidirectional"))
      (node (ref "4") (pin "41") (pinfunction "A18_41") (pintype "bidirectional"))
      (node (ref "5") (pin "41") (pinfunction "A18_41") (pintype "bidirectional"))
      (node (ref "6") (pin "41") (pinfunction "A18_41") (pintype "bidirectional"))
      (node (ref "7") (pin "41") (pinfunction "A18_41") (pintype "bidirectional"))
      (node (ref "RN11") (pin "8") (pinfunction "8_8") (pintype "passive"))
      (node (ref "RN5") (pin "8") (pinfunction "8_8") (pintype "passive"))
      (node (ref "U8") (pin "8") (pinfunction "P3_8") (pintype "input"))
    )
    (net (code "24") (name "A19") (class "Default")
      (node (ref "0") (pin "42") (pinfunction "A19_42") (pintype "bidirectional"))
      (node (ref "1") (pin "42") (pinfunction "A19_42") (pintype "bidirectional"))
      (node (ref "2") (pin "42") (pinfunction "A19_42") (pintype "bidirectional"))
      (node (ref "3") (pin "42") (pinfunction "A19_42") (pintype "bidirectional"))
      (node (ref "4") (pin "42") (pinfunction "A19_42") (pintype "bidirectional"))
      (node (ref "5") (pin "42") (pinfunction "A19_42") (pintype "bidirectional"))
      (node (ref "6") (pin "42") (pinfunction "A19_42") (pintype "bidirectional"))
      (node (ref "7") (pin "42") (pinfunction "A19_42") (pintype "bidirectional"))
      (node (ref "RN2") (pin "8") (pinfunction "8_8") (pintype "passive"))
      (node (ref "RN8") (pin "8") (pinfunction "8_8") (pintype "passive"))
      (node (ref "U8") (pin "11") (pinfunction "P4_11") (pintype "input"))
    )
    (net (code "25") (name "CKLAUX") (class "Default")
      (node (ref "0") (pin "16") (pinfunction "CLKAUX_16") (pintype "bidirectional"))
      (node (ref "1") (pin "16") (pinfunction "CLKAUX_16") (pintype "bidirectional"))
      (node (ref "2") (pin "16") (pinfunction "CLKAUX_16") (pintype "bidirectional"))
      (node (ref "3") (pin "16") (pinfunction "CLKAUX_16") (pintype "bidirectional"))
      (node (ref "4") (pin "16") (pinfunction "CLKAUX_16") (pintype "bidirectional"))
      (node (ref "5") (pin "16") (pinfunction "CLKAUX_16") (pintype "bidirectional"))
      (node (ref "6") (pin "16") (pinfunction "CLKAUX_16") (pintype "bidirectional"))
      (node (ref "7") (pin "16") (pinfunction "CLKAUX_16") (pintype "bidirectional"))
      (node (ref "RN1") (pin "3") (pinfunction "3_3") (pintype "passive"))
      (node (ref "RN7") (pin "3") (pinfunction "3_3") (pintype "passive"))
    )
    (net (code "26") (name "CLK") (class "Default")
      (node (ref "0") (pin "15") (pinfunction "CLK_15") (pintype "bidirectional"))
      (node (ref "1") (pin "15") (pinfunction "CLK_15") (pintype "bidirectional"))
      (node (ref "2") (pin "15") (pinfunction "CLK_15") (pintype "bidirectional"))
      (node (ref "3") (pin "15") (pinfunction "CLK_15") (pintype "bidirectional"))
      (node (ref "4") (pin "15") (pinfunction "CLK_15") (pintype "bidirectional"))
      (node (ref "5") (pin "15") (pinfunction "CLK_15") (pintype "bidirectional"))
      (node (ref "6") (pin "15") (pinfunction "CLK_15") (pintype "bidirectional"))
      (node (ref "7") (pin "15") (pinfunction "CLK_15") (pintype "bidirectional"))
      (node (ref "RN10") (pin "3") (pinfunction "3_3") (pintype "passive"))
      (node (ref "RN4") (pin "3") (pinfunction "3_3") (pintype "passive"))
    )
    (net (code "27") (name "D0") (class "Default")
      (node (ref "0") (pin "43") (pinfunction "D0_43") (pintype "bidirectional"))
      (node (ref "1") (pin "43") (pinfunction "D0_43") (pintype "bidirectional"))
      (node (ref "2") (pin "43") (pinfunction "D0_43") (pintype "bidirectional"))
      (node (ref "3") (pin "43") (pinfunction "D0_43") (pintype "bidirectional"))
      (node (ref "4") (pin "43") (pinfunction "D0_43") (pintype "bidirectional"))
      (node (ref "5") (pin "43") (pinfunction "D0_43") (pintype "bidirectional"))
      (node (ref "6") (pin "43") (pinfunction "D0_43") (pintype "bidirectional"))
      (node (ref "7") (pin "43") (pinfunction "D0_43") (pintype "bidirectional"))
      (node (ref "RN11") (pin "9") (pinfunction "9_9") (pintype "passive"))
      (node (ref "RN5") (pin "9") (pinfunction "9_9") (pintype "passive"))
    )
    (net (code "28") (name "D1") (class "Default")
      (node (ref "0") (pin "44") (pinfunction "D1_44") (pintype "bidirectional"))
      (node (ref "1") (pin "44") (pinfunction "D1_44") (pintype "bidirectional"))
      (node (ref "2") (pin "44") (pinfunction "D1_44") (pintype "bidirectional"))
      (node (ref "3") (pin "44") (pinfunction "D1_44") (pintype "bidirectional"))
      (node (ref "4") (pin "44") (pinfunction "D1_44") (pintype "bidirectional"))
      (node (ref "5") (pin "44") (pinfunction "D1_44") (pintype "bidirectional"))
      (node (ref "6") (pin "44") (pinfunction "D1_44") (pintype "bidirectional"))
      (node (ref "7") (pin "44") (pinfunction "D1_44") (pintype "bidirectional"))
      (node (ref "RN2") (pin "9") (pinfunction "9_9") (pintype "passive"))
      (node (ref "RN8") (pin "9") (pinfunction "9_9") (pintype "passive"))
    )
    (net (code "29") (name "D2") (class "Default")
      (node (ref "0") (pin "45") (pinfunction "D2_45") (pintype "bidirectional"))
      (node (ref "1") (pin "45") (pinfunction "D2_45") (pintype "bidirectional"))
      (node (ref "2") (pin "45") (pinfunction "D2_45") (pintype "bidirectional"))
      (node (ref "3") (pin "45") (pinfunction "D2_45") (pintype "bidirectional"))
      (node (ref "4") (pin "45") (pinfunction "D2_45") (pintype "bidirectional"))
      (node (ref "5") (pin "45") (pinfunction "D2_45") (pintype "bidirectional"))
      (node (ref "6") (pin "45") (pinfunction "D2_45") (pintype "bidirectional"))
      (node (ref "7") (pin "45") (pinfunction "D2_45") (pintype "bidirectional"))
      (node (ref "RN12") (pin "9") (pinfunction "9_9") (pintype "passive"))
      (node (ref "RN6") (pin "9") (pinfunction "9_9") (pintype "passive"))
    )
    (net (code "30") (name "D3") (class "Default")
      (node (ref "0") (pin "46") (pinfunction "D3_46") (pintype "bidirectional"))
      (node (ref "1") (pin "46") (pinfunction "D3_46") (pintype "bidirectional"))
      (node (ref "2") (pin "46") (pinfunction "D3_46") (pintype "bidirectional"))
      (node (ref "3") (pin "46") (pinfunction "D3_46") (pintype "bidirectional"))
      (node (ref "4") (pin "46") (pinfunction "D3_46") (pintype "bidirectional"))
      (node (ref "5") (pin "46") (pinfunction "D3_46") (pintype "bidirectional"))
      (node (ref "6") (pin "46") (pinfunction "D3_46") (pintype "bidirectional"))
      (node (ref "7") (pin "46") (pinfunction "D3_46") (pintype "bidirectional"))
      (node (ref "RN3") (pin "9") (pinfunction "9_9") (pintype "passive"))
      (node (ref "RN9") (pin "9") (pinfunction "9_9") (pintype "passive"))
    )
    (net (code "31") (name "D4") (class "Default")
      (node (ref "0") (pin "47") (pinfunction "D4_47") (pintype "bidirectional"))
      (node (ref "1") (pin "47") (pinfunction "D4_47") (pintype "bidirectional"))
      (node (ref "2") (pin "47") (pinfunction "D4_47") (pintype "bidirectional"))
      (node (ref "3") (pin "47") (pinfunction "D4_47") (pintype "bidirectional"))
      (node (ref "4") (pin "47") (pinfunction "D4_47") (pintype "bidirectional"))
      (node (ref "5") (pin "47") (pinfunction "D4_47") (pintype "bidirectional"))
      (node (ref "6") (pin "47") (pinfunction "D4_47") (pintype "bidirectional"))
      (node (ref "7") (pin "47") (pinfunction "D4_47") (pintype "bidirectional"))
      (node (ref "RN12") (pin "8") (pinfunction "8_8") (pintype "passive"))
      (node (ref "RN6") (pin "8") (pinfunction "8_8") (pintype "passive"))
    )
    (net (code "32") (name "D5") (class "Default")
      (node (ref "0") (pin "48") (pinfunction "D5_48") (pintype "bidirectional"))
      (node (ref "1") (pin "48") (pinfunction "D5_48") (pintype "bidirectional"))
      (node (ref "2") (pin "48") (pinfunction "D5_48") (pintype "bidirectional"))
      (node (ref "3") (pin "48") (pinfunction "D5_48") (pintype "bidirectional"))
      (node (ref "4") (pin "48") (pinfunction "D5_48") (pintype "bidirectional"))
      (node (ref "5") (pin "48") (pinfunction "D5_48") (pintype "bidirectional"))
      (node (ref "6") (pin "48") (pinfunction "D5_48") (pintype "bidirectional"))
      (node (ref "7") (pin "48") (pinfunction "D5_48") (pintype "bidirectional"))
      (node (ref "RN3") (pin "8") (pinfunction "8_8") (pintype "passive"))
      (node (ref "RN9") (pin "8") (pinfunction "8_8") (pintype "passive"))
    )
    (net (code "33") (name "D6") (class "Default")
      (node (ref "0") (pin "49") (pinfunction "D6_49") (pintype "bidirectional"))
      (node (ref "1") (pin "49") (pinfunction "D6_49") (pintype "bidirectional"))
      (node (ref "2") (pin "49") (pinfunction "D6_49") (pintype "bidirectional"))
      (node (ref "3") (pin "49") (pinfunction "D6_49") (pintype "bidirectional"))
      (node (ref "4") (pin "49") (pinfunction "D6_49") (pintype "bidirectional"))
      (node (ref "5") (pin "49") (pinfunction "D6_49") (pintype "bidirectional"))
      (node (ref "6") (pin "49") (pinfunction "D6_49") (pintype "bidirectional"))
      (node (ref "7") (pin "49") (pinfunction "D6_49") (pintype "bidirectional"))
      (node (ref "RN12") (pin "7") (pinfunction "7_7") (pintype "passive"))
      (node (ref "RN6") (pin "7") (pinfunction "7_7") (pintype "passive"))
    )
    (net (code "34") (name "D7") (class "Default")
      (node (ref "0") (pin "50") (pinfunction "D7_50") (pintype "bidirectional"))
      (node (ref "1") (pin "50") (pinfunction "D7_50") (pintype "bidirectional"))
      (node (ref "2") (pin "50") (pinfunction "D7_50") (pintype "bidirectional"))
      (node (ref "3") (pin "50") (pinfunction "D7_50") (pintype "bidirectional"))
      (node (ref "4") (pin "50") (pinfunction "D7_50") (pintype "bidirectional"))
      (node (ref "5") (pin "50") (pinfunction "D7_50") (pintype "bidirectional"))
      (node (ref "6") (pin "50") (pinfunction "D7_50") (pintype "bidirectional"))
      (node (ref "7") (pin "50") (pinfunction "D7_50") (pintype "bidirectional"))
      (node (ref "RN3") (pin "7") (pinfunction "7_7") (pintype "passive"))
      (node (ref "RN9") (pin "7") (pinfunction "7_7") (pintype "passive"))
    )
    (net (code "35") (name "GND") (class "Default")
      (node (ref "0") (pin "3") (pinfunction "GND_3") (pintype "bidirectional"))
      (node (ref "0") (pin "4") (pinfunction "GND_4") (pintype "bidirectional"))
      (node (ref "0") (pin "62") (pinfunction "GND_62") (pintype "bidirectional"))
      (node (ref "1") (pin "3") (pinfunction "GND_3") (pintype "bidirectional"))
      (node (ref "1") (pin "4") (pinfunction "GND_4") (pintype "bidirectional"))
      (node (ref "1") (pin "62") (pinfunction "GND_62") (pintype "bidirectional"))
      (node (ref "2") (pin "3") (pinfunction "GND_3") (pintype "bidirectional"))
      (node (ref "2") (pin "4") (pinfunction "GND_4") (pintype "bidirectional"))
      (node (ref "2") (pin "62") (pinfunction "GND_62") (pintype "bidirectional"))
      (node (ref "3") (pin "3") (pinfunction "GND_3") (pintype "bidirectional"))
      (node (ref "3") (pin "4") (pinfunction "GND_4") (pintype "bidirectional"))
      (node (ref "3") (pin "62") (pinfunction "GND_62") (pintype "bidirectional"))
      (node (ref "4") (pin "3") (pinfunction "GND_3") (pintype "bidirectional"))
      (node (ref "4") (pin "4") (pinfunction "GND_4") (pintype "bidirectional"))
      (node (ref "4") (pin "62") (pinfunction "GND_62") (pintype "bidirectional"))
      (node (ref "5") (pin "3") (pinfunction "GND_3") (pintype "bidirectional"))
      (node (ref "5") (pin "4") (pinfunction "GND_4") (pintype "bidirectional"))
      (node (ref "5") (pin "62") (pinfunction "GND_62") (pintype "bidirectional"))
      (node (ref "6") (pin "3") (pinfunction "GND_3") (pintype "bidirectional"))
      (node (ref "6") (pin "4") (pinfunction "GND_4") (pintype "bidirectional"))
      (node (ref "6") (pin "62") (pinfunction "GND_62") (pintype "bidirectional"))
      (node (ref "7") (pin "3") (pinfunction "GND_3") (pintype "bidirectional"))
      (node (ref "7") (pin "4") (pinfunction "GND_4") (pintype "bidirectional"))
      (node (ref "7") (pin "62") (pinfunction "GND_62") (pintype "bidirectional"))
      (node (ref "C1") (pin "2") (pinfunction "2_2") (pintype "passive"))
      (node (ref "C10") (pin "2") (pinfunction "2_2") (pintype "passive"))
      (node (ref "C11") (pin "2") (pinfunction "2_2") (pintype "passive"))
      (node (ref "C12") (pin "2") (pinfunction "2_2") (pintype "passive"))
      (node (ref "C13") (pin "2") (pinfunction "2_2") (pintype "passive"))
      (node (ref "C14") (pin "2") (pinfunction "2_2") (pintype "passive"))
      (node (ref "C15") (pin "2") (pinfunction "2_2") (pintype "passive"))
      (node (ref "C16") (pin "2") (pinfunction "2_2") (pintype "passive"))
      (node (ref "C17") (pin "2") (pinfunction "2_2") (pintype "passive"))
      (node (ref "C18") (pin "2") (pinfunction "2_2") (pintype "passive"))
      (node (ref "C19") (pin "2") (pinfunction "2_2") (pintype "passive"))
      (node (ref "C2") (pin "2") (pinfunction "2_2") (pintype "passive"))
      (node (ref "C20") (pin "2") (pinfunction "2_2") (pintype "passive"))
      (node (ref "C21") (pin "2") (pinfunction "2_2") (pintype "passive"))
      (node (ref "C22") (pin "2") (pinfunction "2_2") (pintype "passive"))
      (node (ref "C23") (pin "2") (pinfunction "2_2") (pintype "passive"))
      (node (ref "C24") (pin "2") (pinfunction "2_2") (pintype "passive"))
      (node (ref "C25") (pin "2") (pinfunction "2_2") (pintype "passive"))
      (node (ref "C26") (pin "2") (pinfunction "2_2") (pintype "passive"))
      (node (ref "C27") (pin "2") (pinfunction "2_2") (pintype "passive"))
      (node (ref "C28") (pin "2") (pinfunction "2_2") (pintype "passive"))
      (node (ref "C29") (pin "2") (pinfunction "2_2") (pintype "passive"))
      (node (ref "C3") (pin "2") (pinfunction "2_2") (pintype "passive"))
      (node (ref "C30") (pin "2") (pinfunction "2_2") (pintype "passive"))
      (node (ref "C31") (pin "2") (pinfunction "2_2") (pintype "passive"))
      (node (ref "C32") (pin "2") (pinfunction "2_2") (pintype "passive"))
      (node (ref "C34") (pin "2") (pinfunction "2_2") (pintype "passive"))
      (node (ref "C35") (pin "2") (pinfunction "2_2") (pintype "passive"))
      (node (ref "C36") (pin "2") (pinfunction "2_2") (pintype "passive"))
      (node (ref "C37") (pin "2") (pinfunction "2_2") (pintype "passive"))
      (node (ref "C38") (pin "2") (pinfunction "2_2") (pintype "passive"))
      (node (ref "C39") (pin "2") (pinfunction "2_2") (pintype "passive"))
      (node (ref "C4") (pin "2") (pinfunction "2_2") (pintype "passive"))
      (node (ref "C40") (pin "2") (pinfunction "2_2") (pintype "passive"))
      (node (ref "C41") (pin "2") (pinfunction "2_2") (pintype "passive"))
      (node (ref "C42") (pin "2") (pinfunction "2_2") (pintype "passive"))
      (node (ref "C43") (pin "2") (pinfunction "2_2") (pintype "passive"))
      (node (ref "C44") (pin "2") (pinfunction "2_2") (pintype "passive"))
      (node (ref "C45") (pin "-") (pinfunction "-_-") (pintype "passive"))
      (node (ref "C46") (pin "2") (pinfunction "2_2") (pintype "passive"))
      (node (ref "C47") (pin "-") (pinfunction "-_-") (pintype "passive"))
      (node (ref "C48") (pin "-") (pinfunction "-_-") (pintype "passive"))
      (node (ref "C49") (pin "-") (pinfunction "-_-") (pintype "passive"))
      (node (ref "C5") (pin "2") (pinfunction "2_2") (pintype "passive"))
      (node (ref "C50") (pin "-") (pinfunction "-_-") (pintype "passive"))
      (node (ref "C51") (pin "-") (pinfunction "-_-") (pintype "passive"))
      (node (ref "C52") (pin "2") (pinfunction "2_2") (pintype "passive"))
      (node (ref "C53") (pin "2") (pinfunction "2_2") (pintype "passive"))
      (node (ref "C54") (pin "2") (pinfunction "2_2") (pintype "passive"))
      (node (ref "C55") (pin "2") (pinfunction "2_2") (pintype "passive"))
      (node (ref "C57") (pin "-") (pinfunction "-_-") (pintype "passive"))
      (node (ref "C6") (pin "2") (pinfunction "2_2") (pintype "passive"))
      (node (ref "C7") (pin "2") (pinfunction "2_2") (pintype "passive"))
      (node (ref "C8") (pin "2") (pinfunction "2_2") (pintype "passive"))
      (node (ref "C9") (pin "2") (pinfunction "2_2") (pintype "passive"))
      (node (ref "D3") (pin "K") (pinfunction "C_K") (pintype "passive"))
      (node (ref "J1") (pin "15") (pinfunction "GND_15") (pintype "bidirectional"))
      (node (ref "J1") (pin "17") (pinfunction "GND_17") (pintype "bidirectional"))
      (node (ref "J1") (pin "18") (pinfunction "GND_18") (pintype "bidirectional"))
      (node (ref "J1") (pin "19") (pinfunction "GND_19") (pintype "bidirectional"))
      (node (ref "J1") (pin "24") (pinfunction "GND_24") (pintype "bidirectional"))
      (node (ref "J1") (pin "3") (pinfunction "GND_3") (pintype "bidirectional"))
      (node (ref "J1") (pin "5") (pinfunction "GND_5") (pintype "bidirectional"))
      (node (ref "J1") (pin "7") (pinfunction "GND_7") (pintype "bidirectional"))
      (node (ref "J2") (pin "2") (pinfunction "2_2") (pintype "passive"))
      (node (ref "JP5") (pin "3") (pinfunction "3_3") (pintype "passive"))
      (node (ref "Q1") (pin "1") (pinfunction "E_1") (pintype "passive"))
      (node (ref "Q3") (pin "1") (pinfunction "E_1") (pintype "passive"))
      (node (ref "R5") (pin "1") (pinfunction "1_1") (pintype "passive"))
      (node (ref "RN15") (pin "1") (pinfunction "1_1") (pintype "passive"))
      (node (ref "S1") (pin "P$1") (pinfunction "P$1_P$1") (pintype "bidirectional"))
      (node (ref "U5") (pin "2") (pinfunction "GND_2") (pintype "passive"))
      (node (ref "U9") (pin "1") (pinfunction "GND_1") (pintype "power_in"))
    )
    (net (code "36") (name "Net-(C34-Pad1)") (class "Default")
      (node (ref "C34") (pin "1") (pinfunction "1_1") (pintype "passive"))
      (node (ref "C35") (pin "1") (pinfunction "1_1") (pintype "passive"))
      (node (ref "C36") (pin "1") (pinfunction "1_1") (pintype "passive"))
      (node (ref "JP1") (pin "2") (pinfunction "2_2") (pintype "passive"))
      (node (ref "R1") (pin "1") (pinfunction "1_1") (pintype "passive"))
      (node (ref "RN1") (pin "1") (pinfunction "1_1") (pintype "passive"))
      (node (ref "RN2") (pin "1") (pinfunction "1_1") (pintype "passive"))
      (node (ref "RN3") (pin "1") (pinfunction "1_1") (pintype "passive"))
      (node (ref "RN4") (pin "1") (pinfunction "1_1") (pintype "passive"))
      (node (ref "RN5") (pin "1") (pinfunction "1_1") (pintype "passive"))
      (node (ref "RN6") (pin "1") (pinfunction "1_1") (pintype "passive"))
    )
    (net (code "37") (name "Net-(C37-Pad1)") (class "Default")
      (node (ref "C37") (pin "1") (pinfunction "1_1") (pintype "passive"))
      (node (ref "C38") (pin "1") (pinfunction "1_1") (pintype "passive"))
      (node (ref "C39") (pin "1") (pinfunction "1_1") (pintype "passive"))
      (node (ref "JP2") (pin "2") (pinfunction "2_2") (pintype "passive"))
      (node (ref "R2") (pin "1") (pinfunction "1_1") (pintype "passive"))
      (node (ref "RN10") (pin "1") (pinfunction "1_1") (pintype "passive"))
      (node (ref "RN11") (pin "1") (pinfunction "1_1") (pintype "passive"))
      (node (ref "RN12") (pin "1") (pinfunction "1_1") (pintype "passive"))
      (node (ref "RN7") (pin "1") (pinfunction "1_1") (pintype "passive"))
      (node (ref "RN8") (pin "1") (pinfunction "1_1") (pintype "passive"))
      (node (ref "RN9") (pin "1") (pinfunction "1_1") (pintype "passive"))
    )
    (net (code "38") (name "Net-(C56-Pad2)") (class "Default")
      (node (ref "C56") (pin "2") (pinfunction "2_2") (pintype "passive"))
      (node (ref "JP5") (pin "2") (pinfunction "2_2") (pintype "passive"))
    )
    (net (code "39") (name "Net-(D1-PadA)") (class "Default")
      (node (ref "D1") (pin "A") (pinfunction "A_A") (pintype "passive"))
      (node (ref "JP3") (pin "1") (pinfunction "1_1") (pintype "passive"))
    )
    (net (code "40") (name "Net-(D2-C)") (class "Default")
      (node (ref "D2") (pin "K") (pinfunction "C_K") (pintype "passive"))
      (node (ref "JP5") (pin "1") (pinfunction "1_1") (pintype "passive"))
      (node (ref "Q1") (pin "3") (pinfunction "C_3") (pintype "passive"))
    )
    (net (code "41") (name "Net-(D2-PadA)") (class "Default")
      (node (ref "D2") (pin "A") (pinfunction "A_A") (pintype "passive"))
      (node (ref "R11") (pin "1") (pinfunction "1_1") (pintype "passive"))
    )
    (net (code "42") (name "Net-(D3-PadA)") (class "Default")
      (node (ref "D3") (pin "A") (pinfunction "A_A") (pintype "passive"))
      (node (ref "R12") (pin "1") (pinfunction "1_1") (pintype "passive"))
    )
    (net (code "43") (name "Net-(J1-PS_ON)") (class "Default")
      (node (ref "J1") (pin "16") (pinfunction "PS_ON_16") (pintype "bidirectional"))
      (node (ref "J2") (pin "1") (pinfunction "1_1") (pintype "passive"))
      (node (ref "S1") (pin "P$2") (pinfunction "P$2_P$2") (pintype "bidirectional"))
    )
    (net (code "44") (name "Net-(Q1-B)") (class "Default")
      (node (ref "Q1") (pin "2") (pinfunction "B_2") (pintype "passive"))
      (node (ref "R6") (pin "2") (pinfunction "2_2") (pintype "passive"))
    )
    (net (code "45") (name "Net-(Q2-B)") (class "Default")
      (node (ref "Q2") (pin "2") (pinfunction "B_2") (pintype "passive"))
      (node (ref "R10") (pin "2") (pinfunction "2_2") (pintype "passive"))
    )
    (net (code "46") (name "Net-(Q2-C)") (class "Default")
      (node (ref "Q2") (pin "3") (pinfunction "C_3") (pintype "passive"))
      (node (ref "R12") (pin "2") (pinfunction "2_2") (pintype "passive"))
    )
    (net (code "47") (name "Net-(Q3-B)") (class "Default")
      (node (ref "Q3") (pin "2") (pinfunction "B_2") (pintype "passive"))
      (node (ref "R9") (pin "2") (pinfunction "2_2") (pintype "passive"))
    )
    (net (code "48") (name "Net-(Q3-C)") (class "Default")
      (node (ref "JP7") (pin "1") (pinfunction "1_1") (pintype "passive"))
      (node (ref "Q3") (pin "3") (pinfunction "C_3") (pintype "passive"))
    )
    (net (code "49") (name "Net-(U1A-I0)") (class "Default")
      (node (ref "U1") (pin "1") (pinfunction "I0_1") (pintype "input"))
      (node (ref "U2") (pin "2") (pinfunction "O_2") (pintype "output"))
    )
    (net (code "50") (name "Net-(U1A-O)") (class "Default")
      (node (ref "R3") (pin "1") (pinfunction "1_1") (pintype "passive"))
      (node (ref "U1") (pin "3") (pinfunction "O_3") (pintype "output"))
    )
    (net (code "51") (name "Net-(U2A-I)") (class "Default")
      (node (ref "U2") (pin "1") (pinfunction "I_1") (pintype "input"))
      (node (ref "U3") (pin "8") (pinfunction "O_8") (pintype "output"))
    )
    (net (code "52") (name "Net-(U2B-I)") (class "Default")
      (node (ref "U2") (pin "3") (pinfunction "I_3") (pintype "input"))
      (node (ref "U4") (pin "8") (pinfunction "O_8") (pintype "output"))
    )
    (net (code "53") (name "Net-(U2B-O)") (class "Default")
      (node (ref "R4") (pin "1") (pinfunction "1_1") (pintype "passive"))
      (node (ref "U2") (pin "4") (pinfunction "O_4") (pintype "output"))
    )
    (net (code "54") (name "Net-(U5-VI)") (class "Default")
      (node (ref "C44") (pin "1") (pinfunction "1_1") (pintype "passive"))
      (node (ref "D1") (pin "C") (pinfunction "C_C") (pintype "passive"))
      (node (ref "U5") (pin "1") (pinfunction "VI_1") (pintype "input"))
    )
    (net (code "55") (name "Net-(U5-VO)") (class "Default")
      (node (ref "C45") (pin "+") (pinfunction "+_+") (pintype "passive"))
      (node (ref "C46") (pin "1") (pinfunction "1_1") (pintype "passive"))
      (node (ref "JP1") (pin "3") (pinfunction "3_3") (pintype "passive"))
      (node (ref "JP2") (pin "3") (pinfunction "3_3") (pintype "passive"))
      (node (ref "U5") (pin "3") (pinfunction "VO_3") (pintype "passive"))
    )
    (net (code "56") (name "Net-(U8A-G)") (class "Default")
      (node (ref "JP4") (pin "2") (pinfunction "2_2") (pintype "passive"))
      (node (ref "R5") (pin "2") (pinfunction "2_2") (pintype "passive"))
      (node (ref "U8") (pin "1") (pinfunction "G_1") (pintype "input"))
    )
    (net (code "57") (name "Net-(U8A-Q0)") (class "Default")
      (node (ref "RN15") (pin "9") (pinfunction "9_9") (pintype "passive"))
      (node (ref "S2") (pin "9") (pinfunction "9_9") (pintype "passive"))
      (node (ref "U8") (pin "3") (pinfunction "Q0_3") (pintype "input"))
    )
    (net (code "58") (name "Net-(U8A-Q1)") (class "Default")
      (node (ref "RN15") (pin "7") (pinfunction "7_7") (pintype "passive"))
      (node (ref "S2") (pin "11") (pinfunction "11_11") (pintype "passive"))
      (node (ref "U8") (pin "5") (pinfunction "Q1_5") (pintype "input"))
    )
    (net (code "59") (name "Net-(U8A-Q2)") (class "Default")
      (node (ref "RN15") (pin "5") (pinfunction "5_5") (pintype "passive"))
      (node (ref "S2") (pin "13") (pinfunction "13_13") (pintype "passive"))
      (node (ref "U8") (pin "7") (pinfunction "Q2_7") (pintype "input"))
    )
    (net (code "60") (name "Net-(U8A-Q3)") (class "Default")
      (node (ref "RN15") (pin "3") (pinfunction "3_3") (pintype "passive"))
      (node (ref "S2") (pin "15") (pinfunction "15_15") (pintype "passive"))
      (node (ref "U8") (pin "9") (pinfunction "Q3_9") (pintype "input"))
    )
    (net (code "61") (name "Net-(U8A-Q4)") (class "Default")
      (node (ref "RN15") (pin "2") (pinfunction "2_2") (pintype "passive"))
      (node (ref "S2") (pin "16") (pinfunction "16_16") (pintype "passive"))
      (node (ref "U8") (pin "12") (pinfunction "Q4_12") (pintype "input"))
    )
    (net (code "62") (name "Net-(U8A-Q5)") (class "Default")
      (node (ref "RN15") (pin "4") (pinfunction "4_4") (pintype "passive"))
      (node (ref "S2") (pin "14") (pinfunction "14_14") (pintype "passive"))
      (node (ref "U8") (pin "14") (pinfunction "Q5_14") (pintype "input"))
    )
    (net (code "63") (name "Net-(U8A-Q6)") (class "Default")
      (node (ref "RN15") (pin "6") (pinfunction "6_6") (pintype "passive"))
      (node (ref "S2") (pin "12") (pinfunction "12_12") (pintype "passive"))
      (node (ref "U8") (pin "16") (pinfunction "Q6_16") (pintype "input"))
    )
    (net (code "64") (name "Net-(U8A-Q7)") (class "Default")
      (node (ref "RN15") (pin "8") (pinfunction "8_8") (pintype "passive"))
      (node (ref "S2") (pin "10") (pinfunction "10_10") (pintype "passive"))
      (node (ref "U8") (pin "18") (pinfunction "Q7_18") (pintype "input"))
    )
    (net (code "65") (name "Net-(U9-CON)") (class "Default")
      (node (ref "C55") (pin "1") (pinfunction "1_1") (pintype "passive"))
      (node (ref "U9") (pin "5") (pinfunction "CON_5") (pintype "input"))
    )
    (net (code "66") (name "Net-(U9-DIS)") (class "Default")
      (node (ref "C57") (pin "+") (pinfunction "+_+") (pintype "passive"))
      (node (ref "R8") (pin "2") (pinfunction "2_2") (pintype "passive"))
      (node (ref "U9") (pin "6") (pinfunction "TRE_6") (pintype "input"))
      (node (ref "U9") (pin "7") (pinfunction "DIS_7") (pintype "input"))
    )
    (net (code "67") (name "Net-(U9-OUT)") (class "Default")
      (node (ref "R9") (pin "1") (pinfunction "1_1") (pintype "passive"))
      (node (ref "U9") (pin "3") (pinfunction "OUT_3") (pintype "output"))
    )
    (net (code "68") (name "Net-(U9-TRI)") (class "Default")
      (node (ref "C56") (pin "1") (pinfunction "1_1") (pintype "passive"))
      (node (ref "R7") (pin "2") (pinfunction "2_2") (pintype "passive"))
      (node (ref "U9") (pin "2") (pinfunction "TRI_2") (pintype "input"))
    )
    (net (code "69") (name "Net-(U9-VCC+)") (class "Default")
      (node (ref "C54") (pin "1") (pinfunction "1_1") (pintype "passive"))
      (node (ref "JP6") (pin "2") (pinfunction "2_2") (pintype "passive"))
      (node (ref "R7") (pin "1") (pinfunction "1_1") (pintype "passive"))
      (node (ref "R8") (pin "1") (pinfunction "1_1") (pintype "passive"))
      (node (ref "U9") (pin "4") (pinfunction "/RES_4") (pintype "input"))
      (node (ref "U9") (pin "8") (pinfunction "VCC+_8") (pintype "power_in"))
    )
    (net (code "70") (name "PG") (class "Default")
      (node (ref "J1") (pin "8") (pinfunction "PWR_OK_8") (pintype "bidirectional"))
      (node (ref "R6") (pin "1") (pinfunction "1_1") (pintype "passive"))
    )
    (net (code "71") (name "VCC") (class "Default")
      (node (ref "0") (pin "5") (pinfunction "+5V_5") (pintype "bidirectional"))
      (node (ref "0") (pin "6") (pinfunction "+5V_6") (pintype "bidirectional"))
      (node (ref "1") (pin "5") (pinfunction "+5V_5") (pintype "bidirectional"))
      (node (ref "1") (pin "6") (pinfunction "+5V_6") (pintype "bidirectional"))
      (node (ref "2") (pin "5") (pinfunction "+5V_5") (pintype "bidirectional"))
      (node (ref "2") (pin "6") (pinfunction "+5V_6") (pintype "bidirectional"))
      (node (ref "3") (pin "5") (pinfunction "+5V_5") (pintype "bidirectional"))
      (node (ref "3") (pin "6") (pinfunction "+5V_6") (pintype "bidirectional"))
      (node (ref "4") (pin "5") (pinfunction "+5V_5") (pintype "bidirectional"))
      (node (ref "4") (pin "6") (pinfunction "+5V_6") (pintype "bidirectional"))
      (node (ref "5") (pin "5") (pinfunction "+5V_5") (pintype "bidirectional"))
      (node (ref "5") (pin "6") (pinfunction "+5V_6") (pintype "bidirectional"))
      (node (ref "6") (pin "5") (pinfunction "+5V_5") (pintype "bidirectional"))
      (node (ref "6") (pin "6") (pinfunction "+5V_6") (pintype "bidirectional"))
      (node (ref "7") (pin "5") (pinfunction "+5V_5") (pintype "bidirectional"))
      (node (ref "7") (pin "6") (pinfunction "+5V_6") (pintype "bidirectional"))
      (node (ref "C10") (pin "1") (pinfunction "1_1") (pintype "passive"))
      (node (ref "C14") (pin "1") (pinfunction "1_1") (pintype "passive"))
      (node (ref "C18") (pin "1") (pinfunction "1_1") (pintype "passive"))
      (node (ref "C2") (pin "1") (pinfunction "1_1") (pintype "passive"))
      (node (ref "C22") (pin "1") (pinfunction "1_1") (pintype "passive"))
      (node (ref "C26") (pin "1") (pinfunction "1_1") (pintype "passive"))
      (node (ref "C30") (pin "1") (pinfunction "1_1") (pintype "passive"))
      (node (ref "C40") (pin "1") (pinfunction "1_1") (pintype "passive"))
      (node (ref "C41") (pin "1") (pinfunction "1_1") (pintype "passive"))
      (node (ref "C42") (pin "1") (pinfunction "1_1") (pintype "passive"))
      (node (ref "C43") (pin "1") (pinfunction "1_1") (pintype "passive"))
      (node (ref "C49") (pin "+") (pinfunction "+_+") (pintype "passive"))
      (node (ref "C52") (pin "1") (pinfunction "1_1") (pintype "passive"))
      (node (ref "C53") (pin "1") (pinfunction "1_1") (pintype "passive"))
      (node (ref "C6") (pin "1") (pinfunction "1_1") (pintype "passive"))
      (node (ref "J1") (pin "21") (pinfunction "5V_21") (pintype "bidirectional"))
      (node (ref "J1") (pin "22") (pinfunction "5V_22") (pintype "bidirectional"))
      (node (ref "J1") (pin "23") (pinfunction "5V_23") (pintype "bidirectional"))
      (node (ref "J1") (pin "4") (pinfunction "5V_4") (pintype "bidirectional"))
      (node (ref "J1") (pin "6") (pinfunction "5V_6") (pintype "bidirectional"))
      (node (ref "JP1") (pin "1") (pinfunction "1_1") (pintype "passive"))
      (node (ref "JP2") (pin "1") (pinfunction "1_1") (pintype "passive"))
      (node (ref "JP3") (pin "2") (pinfunction "2_2") (pintype "passive"))
      (node (ref "JP4") (pin "1") (pinfunction "1_1") (pintype "passive"))
      (node (ref "JP6") (pin "1") (pinfunction "1_1") (pintype "passive"))
      (node (ref "Q2") (pin "1") (pinfunction "E_1") (pintype "passive"))
      (node (ref "R11") (pin "2") (pinfunction "2_2") (pintype "passive"))
      (node (ref "RN13") (pin "1") (pinfunction "1_1") (pintype "passive"))
      (node (ref "RN14") (pin "1") (pinfunction "1_1") (pintype "passive"))
      (node (ref "S2") (pin "1") (pinfunction "1_1") (pintype "passive"))
      (node (ref "S2") (pin "2") (pinfunction "2_2") (pintype "passive"))
      (node (ref "S2") (pin "3") (pinfunction "3_3") (pintype "passive"))
      (node (ref "S2") (pin "4") (pinfunction "4_4") (pintype "passive"))
      (node (ref "S2") (pin "5") (pinfunction "5_5") (pintype "passive"))
      (node (ref "S2") (pin "6") (pinfunction "6_6") (pintype "passive"))
      (node (ref "S2") (pin "7") (pinfunction "7_7") (pintype "passive"))
      (node (ref "S2") (pin "8") (pinfunction "8_8") (pintype "passive"))
      (node (ref "U1") (pin "10") (pinfunction "I1_10") (pintype "input"))
      (node (ref "U1") (pin "12") (pinfunction "I0_12") (pintype "input"))
      (node (ref "U1") (pin "13") (pinfunction "I1_13") (pintype "input"))
      (node (ref "U1") (pin "4") (pinfunction "I0_4") (pintype "input"))
      (node (ref "U1") (pin "5") (pinfunction "I1_5") (pintype "input"))
      (node (ref "U1") (pin "9") (pinfunction "I0_9") (pintype "input"))
      (node (ref "U2") (pin "11") (pinfunction "I_11") (pintype "input"))
      (node (ref "U2") (pin "13") (pinfunction "I_13") (pintype "input"))
      (node (ref "U2") (pin "5") (pinfunction "I_5") (pintype "input"))
      (node (ref "U2") (pin "9") (pinfunction "I_9") (pintype "input"))
      (node (ref "U7") (pin "6") (pinfunction "G1_6") (pintype "input"))
    )
    (net (code "72") (name "unconnected-(J1-3.3V-Pad12)") (class "Default")
      (node (ref "J1") (pin "12") (pinfunction "3.3V_12") (pintype "bidirectional"))
    )
    (net (code "73") (name "unconnected-(J1-NC-Pad20)") (class "Default")
      (node (ref "J1") (pin "20") (pinfunction "NC_20") (pintype "bidirectional"))
    )
    (net (code "74") (name "unconnected-(S1-PadP$3)") (class "Default")
      (node (ref "S1") (pin "P$3") (pinfunction "P$3_P$3") (pintype "bidirectional"))
    )
    (net (code "75") (name "unconnected-(U1B-O-Pad6)") (class "Default")
      (node (ref "U1") (pin "6") (pinfunction "O_6") (pintype "output"))
    )
    (net (code "76") (name "unconnected-(U1C-O-Pad8)") (class "Default")
      (node (ref "U1") (pin "8") (pinfunction "O_8") (pintype "output"))
    )
    (net (code "77") (name "unconnected-(U1D-O-Pad11)") (class "Default")
      (node (ref "U1") (pin "11") (pinfunction "O_11") (pintype "output"))
    )
    (net (code "78") (name "unconnected-(U2C-O-Pad6)") (class "Default")
      (node (ref "U2") (pin "6") (pinfunction "O_6") (pintype "output"))
    )
    (net (code "79") (name "unconnected-(U2D-O-Pad8)") (class "Default")
      (node (ref "U2") (pin "8") (pinfunction "O_8") (pintype "output"))
    )
    (net (code "80") (name "unconnected-(U2E-O-Pad10)") (class "Default")
      (node (ref "U2") (pin "10") (pinfunction "O_10") (pintype "output"))
    )
    (net (code "81") (name "unconnected-(U2F-O-Pad12)") (class "Default")
      (node (ref "U2") (pin "12") (pinfunction "O_12") (pintype "output"))
    )
    (net (code "82") (name "~{BUSACK}") (class "Default")
      (node (ref "0") (pin "20") (pinfunction "~{BUSACK}_20") (pintype "bidirectional"))
      (node (ref "1") (pin "20") (pinfunction "~{BUSACK}_20") (pintype "bidirectional"))
      (node (ref "2") (pin "20") (pinfunction "~{BUSACK}_20") (pintype "bidirectional"))
      (node (ref "3") (pin "20") (pinfunction "~{BUSACK}_20") (pintype "bidirectional"))
      (node (ref "4") (pin "20") (pinfunction "~{BUSACK}_20") (pintype "bidirectional"))
      (node (ref "5") (pin "20") (pinfunction "~{BUSACK}_20") (pintype "bidirectional"))
      (node (ref "6") (pin "20") (pinfunction "~{BUSACK}_20") (pintype "bidirectional"))
      (node (ref "7") (pin "20") (pinfunction "~{BUSACK}_20") (pintype "bidirectional"))
      (node (ref "RN1") (pin "5") (pinfunction "5_5") (pintype "passive"))
      (node (ref "RN7") (pin "5") (pinfunction "5_5") (pintype "passive"))
    )
    (net (code "83") (name "~{BUSRQ0}") (class "Default")
      (node (ref "0") (pin "10") (pinfunction "~{BUSRQ}_10") (pintype "bidirectional"))
      (node (ref "RN14") (pin "2") (pinfunction "2_2") (pintype "passive"))
      (node (ref "U4") (pin "1") (pinfunction "I0_1") (pintype "input"))
    )
    (net (code "84") (name "~{BUSRQ1}") (class "Default")
      (node (ref "1") (pin "10") (pinfunction "~{BUSRQ}_10") (pintype "bidirectional"))
      (node (ref "RN14") (pin "3") (pinfunction "3_3") (pintype "passive"))
      (node (ref "U4") (pin "2") (pinfunction "I1_2") (pintype "input"))
    )
    (net (code "85") (name "~{BUSRQ2}") (class "Default")
      (node (ref "2") (pin "10") (pinfunction "~{BUSRQ}_10") (pintype "bidirectional"))
      (node (ref "RN14") (pin "4") (pinfunction "4_4") (pintype "passive"))
      (node (ref "U4") (pin "3") (pinfunction "I2_3") (pintype "input"))
    )
    (net (code "86") (name "~{BUSRQ3}") (class "Default")
      (node (ref "3") (pin "10") (pinfunction "~{BUSRQ}_10") (pintype "bidirectional"))
      (node (ref "RN14") (pin "5") (pinfunction "5_5") (pintype "passive"))
      (node (ref "U4") (pin "4") (pinfunction "I3_4") (pintype "input"))
    )
    (net (code "87") (name "~{BUSRQ4}") (class "Default")
      (node (ref "4") (pin "10") (pinfunction "~{BUSRQ}_10") (pintype "bidirectional"))
      (node (ref "RN14") (pin "6") (pinfunction "6_6") (pintype "passive"))
      (node (ref "U4") (pin "5") (pinfunction "I4_5") (pintype "input"))
    )
    (net (code "88") (name "~{BUSRQ5}") (class "Default")
      (node (ref "5") (pin "10") (pinfunction "~{BUSRQ}_10") (pintype "bidirectional"))
      (node (ref "RN14") (pin "7") (pinfunction "7_7") (pintype "passive"))
      (node (ref "U4") (pin "6") (pinfunction "I5_6") (pintype "input"))
    )
    (net (code "89") (name "~{BUSRQ6}") (class "Default")
      (node (ref "6") (pin "10") (pinfunction "~{BUSRQ}_10") (pintype "bidirectional"))
      (node (ref "RN14") (pin "8") (pinfunction "8_8") (pintype "passive"))
      (node (ref "U4") (pin "11") (pinfunction "I6_11") (pintype "input"))
    )
    (net (code "90") (name "~{BUSRQ7}") (class "Default")
      (node (ref "7") (pin "10") (pinfunction "~{BUSRQ}_10") (pintype "bidirectional"))
      (node (ref "RN14") (pin "9") (pinfunction "9_9") (pintype "passive"))
      (node (ref "U4") (pin "12") (pinfunction "I7_12") (pintype "input"))
    )
    (net (code "91") (name "~{CBR}") (class "Default")
      (node (ref "0") (pin "12") (pinfunction "~{CBR}_12") (pintype "bidirectional"))
      (node (ref "1") (pin "12") (pinfunction "~{CBR}_12") (pintype "bidirectional"))
      (node (ref "2") (pin "12") (pinfunction "~{CBR}_12") (pintype "bidirectional"))
      (node (ref "3") (pin "12") (pinfunction "~{CBR}_12") (pintype "bidirectional"))
      (node (ref "4") (pin "12") (pinfunction "~{CBR}_12") (pintype "bidirectional"))
      (node (ref "5") (pin "12") (pinfunction "~{CBR}_12") (pintype "bidirectional"))
      (node (ref "6") (pin "12") (pinfunction "~{CBR}_12") (pintype "bidirectional"))
      (node (ref "7") (pin "12") (pinfunction "~{CBR}_12") (pintype "bidirectional"))
      (node (ref "R1") (pin "2") (pinfunction "2_2") (pintype "passive"))
      (node (ref "R2") (pin "2") (pinfunction "2_2") (pintype "passive"))
      (node (ref "R4") (pin "2") (pinfunction "2_2") (pintype "passive"))
    )
    (net (code "92") (name "~{CINH}") (class "Default")
      (node (ref "0") (pin "13") (pinfunction "~{CINH}_13") (pintype "bidirectional"))
      (node (ref "1") (pin "13") (pinfunction "~{CINH}_13") (pintype "bidirectional"))
      (node (ref "2") (pin "13") (pinfunction "~{CINH}_13") (pintype "bidirectional"))
      (node (ref "3") (pin "13") (pinfunction "~{CINH}_13") (pintype "bidirectional"))
      (node (ref "4") (pin "13") (pinfunction "~{CINH}_13") (pintype "bidirectional"))
      (node (ref "5") (pin "13") (pinfunction "~{CINH}_13") (pintype "bidirectional"))
      (node (ref "6") (pin "13") (pinfunction "~{CINH}_13") (pintype "bidirectional"))
      (node (ref "7") (pin "13") (pinfunction "~{CINH}_13") (pintype "bidirectional"))
      (node (ref "R3") (pin "2") (pinfunction "2_2") (pintype "passive"))
      (node (ref "RN10") (pin "2") (pinfunction "2_2") (pintype "passive"))
      (node (ref "RN4") (pin "2") (pinfunction "2_2") (pintype "passive"))
    )
    (net (code "93") (name "~{CS0}") (class "Default")
      (node (ref "0") (pin "9") (pinfunction "~{CSX}_9") (pintype "bidirectional"))
      (node (ref "U7") (pin "15") (pinfunction "Y0_15") (pintype "output"))
    )
    (net (code "94") (name "~{CS1}") (class "Default")
      (node (ref "1") (pin "9") (pinfunction "~{CSX}_9") (pintype "bidirectional"))
      (node (ref "U7") (pin "14") (pinfunction "Y1_14") (pintype "output"))
    )
    (net (code "95") (name "~{CS2}") (class "Default")
      (node (ref "2") (pin "9") (pinfunction "~{CSX}_9") (pintype "bidirectional"))
      (node (ref "U7") (pin "13") (pinfunction "Y2_13") (pintype "output"))
    )
    (net (code "96") (name "~{CS3}") (class "Default")
      (node (ref "3") (pin "9") (pinfunction "~{CSX}_9") (pintype "bidirectional"))
      (node (ref "U7") (pin "12") (pinfunction "Y3_12") (pintype "output"))
    )
    (net (code "97") (name "~{CS4}") (class "Default")
      (node (ref "4") (pin "9") (pinfunction "~{CSX}_9") (pintype "bidirectional"))
      (node (ref "U7") (pin "11") (pinfunction "Y4_11") (pintype "output"))
    )
    (net (code "98") (name "~{CS5}") (class "Default")
      (node (ref "5") (pin "9") (pinfunction "~{CSX}_9") (pintype "bidirectional"))
      (node (ref "U7") (pin "10") (pinfunction "Y5_10") (pintype "output"))
    )
    (net (code "99") (name "~{CS6}") (class "Default")
      (node (ref "6") (pin "9") (pinfunction "~{CSX}_9") (pintype "bidirectional"))
      (node (ref "U7") (pin "9") (pinfunction "Y6_9") (pintype "output"))
    )
    (net (code "100") (name "~{CS7}") (class "Default")
      (node (ref "7") (pin "9") (pinfunction "~{CSX}_9") (pintype "bidirectional"))
      (node (ref "U7") (pin "7") (pinfunction "Y7_7") (pintype "output"))
    )
    (net (code "101") (name "~{FETCH}") (class "Default")
      (node (ref "0") (pin "19") (pinfunction "~{FETCH}_19") (pintype "bidirectional"))
      (node (ref "1") (pin "19") (pinfunction "~{FETCH}_19") (pintype "bidirectional"))
      (node (ref "2") (pin "19") (pinfunction "~{FETCH}_19") (pintype "bidirectional"))
      (node (ref "3") (pin "19") (pinfunction "~{FETCH}_19") (pintype "bidirectional"))
      (node (ref "4") (pin "19") (pinfunction "~{FETCH}_19") (pintype "bidirectional"))
      (node (ref "5") (pin "19") (pinfunction "~{FETCH}_19") (pintype "bidirectional"))
      (node (ref "6") (pin "19") (pinfunction "~{FETCH}_19") (pintype "bidirectional"))
      (node (ref "7") (pin "19") (pinfunction "~{FETCH}_19") (pintype "bidirectional"))
      (node (ref "RN10") (pin "5") (pinfunction "5_5") (pintype "passive"))
      (node (ref "RN4") (pin "5") (pinfunction "5_5") (pintype "passive"))
    )
    (net (code "102") (name "~{HALT}") (class "Default")
      (node (ref "0") (pin "17") (pinfunction "~{HALT}_17") (pintype "bidirectional"))
      (node (ref "1") (pin "17") (pinfunction "~{HALT}_17") (pintype "bidirectional"))
      (node (ref "2") (pin "17") (pinfunction "~{HALT}_17") (pintype "bidirectional"))
      (node (ref "3") (pin "17") (pinfunction "~{HALT}_17") (pintype "bidirectional"))
      (node (ref "4") (pin "17") (pinfunction "~{HALT}_17") (pintype "bidirectional"))
      (node (ref "5") (pin "17") (pinfunction "~{HALT}_17") (pintype "bidirectional"))
      (node (ref "6") (pin "17") (pinfunction "~{HALT}_17") (pintype "bidirectional"))
      (node (ref "7") (pin "17") (pinfunction "~{HALT}_17") (pintype "bidirectional"))
      (node (ref "RN10") (pin "4") (pinfunction "4_4") (pintype "passive"))
      (node (ref "RN4") (pin "4") (pinfunction "4_4") (pintype "passive"))
    )
    (net (code "103") (name "~{INH0}") (class "Default")
      (node (ref "0") (pin "11") (pinfunction "~{INH}_11") (pintype "bidirectional"))
      (node (ref "RN13") (pin "2") (pinfunction "2_2") (pintype "passive"))
      (node (ref "U3") (pin "1") (pinfunction "I0_1") (pintype "input"))
    )
    (net (code "104") (name "~{INH1}") (class "Default")
      (node (ref "1") (pin "11") (pinfunction "~{INH}_11") (pintype "bidirectional"))
      (node (ref "RN13") (pin "3") (pinfunction "3_3") (pintype "passive"))
      (node (ref "U3") (pin "2") (pinfunction "I1_2") (pintype "input"))
    )
    (net (code "105") (name "~{INH2}") (class "Default")
      (node (ref "2") (pin "11") (pinfunction "~{INH}_11") (pintype "bidirectional"))
      (node (ref "RN13") (pin "4") (pinfunction "4_4") (pintype "passive"))
      (node (ref "U3") (pin "3") (pinfunction "I2_3") (pintype "input"))
    )
    (net (code "106") (name "~{INH3}") (class "Default")
      (node (ref "3") (pin "11") (pinfunction "~{INH}_11") (pintype "bidirectional"))
      (node (ref "RN13") (pin "5") (pinfunction "5_5") (pintype "passive"))
      (node (ref "U3") (pin "4") (pinfunction "I3_4") (pintype "input"))
    )
    (net (code "107") (name "~{INH4}") (class "Default")
      (node (ref "4") (pin "11") (pinfunction "~{INH}_11") (pintype "bidirectional"))
      (node (ref "RN13") (pin "6") (pinfunction "6_6") (pintype "passive"))
      (node (ref "U3") (pin "5") (pinfunction "I4_5") (pintype "input"))
    )
    (net (code "108") (name "~{INH5}") (class "Default")
      (node (ref "5") (pin "11") (pinfunction "~{INH}_11") (pintype "bidirectional"))
      (node (ref "RN13") (pin "7") (pinfunction "7_7") (pintype "passive"))
      (node (ref "U3") (pin "6") (pinfunction "I5_6") (pintype "input"))
    )
    (net (code "109") (name "~{INH6}") (class "Default")
      (node (ref "6") (pin "11") (pinfunction "~{INH}_11") (pintype "bidirectional"))
      (node (ref "RN13") (pin "8") (pinfunction "8_8") (pintype "passive"))
      (node (ref "U3") (pin "11") (pinfunction "I6_11") (pintype "input"))
    )
    (net (code "110") (name "~{INH7}") (class "Default")
      (node (ref "7") (pin "11") (pinfunction "~{INH}_11") (pintype "bidirectional"))
      (node (ref "RN13") (pin "9") (pinfunction "9_9") (pintype "passive"))
      (node (ref "U3") (pin "12") (pinfunction "I7_12") (pintype "input"))
    )
    (net (code "111") (name "~{INHPCS}") (class "Default")
      (node (ref "U1") (pin "2") (pinfunction "I1_2") (pintype "input"))
      (node (ref "U7") (pin "5") (pinfunction "G2B_5") (pintype "input"))
      (node (ref "U8") (pin "19") (pinfunction "P=Q_19") (pintype "output"))
    )
    (net (code "112") (name "~{INT}") (class "Default")
      (node (ref "0") (pin "51") (pinfunction "~{INT}_51") (pintype "bidirectional"))
      (node (ref "1") (pin "51") (pinfunction "~{INT}_51") (pintype "bidirectional"))
      (node (ref "2") (pin "51") (pinfunction "~{INT}_51") (pintype "bidirectional"))
      (node (ref "3") (pin "51") (pinfunction "~{INT}_51") (pintype "bidirectional"))
      (node (ref "4") (pin "51") (pinfunction "~{INT}_51") (pintype "bidirectional"))
      (node (ref "5") (pin "51") (pinfunction "~{INT}_51") (pintype "bidirectional"))
      (node (ref "6") (pin "51") (pinfunction "~{INT}_51") (pintype "bidirectional"))
      (node (ref "7") (pin "51") (pinfunction "~{INT}_51") (pintype "bidirectional"))
      (node (ref "RN12") (pin "6") (pinfunction "6_6") (pintype "passive"))
      (node (ref "RN6") (pin "6") (pinfunction "6_6") (pintype "passive"))
    )
    (net (code "113") (name "~{IRQ0}") (class "Default")
      (node (ref "0") (pin "52") (pinfunction "~{IRQX}_52") (pintype "bidirectional"))
      (node (ref "0") (pin "53") (pinfunction "~{IRQ0}_53") (pintype "bidirectional"))
      (node (ref "1") (pin "53") (pinfunction "~{IRQ0}_53") (pintype "bidirectional"))
      (node (ref "2") (pin "53") (pinfunction "~{IRQ0}_53") (pintype "bidirectional"))
      (node (ref "3") (pin "53") (pinfunction "~{IRQ0}_53") (pintype "bidirectional"))
      (node (ref "4") (pin "53") (pinfunction "~{IRQ0}_53") (pintype "bidirectional"))
      (node (ref "5") (pin "53") (pinfunction "~{IRQ0}_53") (pintype "bidirectional"))
      (node (ref "6") (pin "53") (pinfunction "~{IRQ0}_53") (pintype "bidirectional"))
      (node (ref "7") (pin "53") (pinfunction "~{IRQ0}_53") (pintype "bidirectional"))
      (node (ref "RN3") (pin "6") (pinfunction "6_6") (pintype "passive"))
      (node (ref "RN9") (pin "6") (pinfunction "6_6") (pintype "passive"))
    )
    (net (code "114") (name "~{IRQ1}") (class "Default")
      (node (ref "0") (pin "54") (pinfunction "~{IRQ1}_54") (pintype "bidirectional"))
      (node (ref "1") (pin "52") (pinfunction "~{IRQX}_52") (pintype "bidirectional"))
      (node (ref "1") (pin "54") (pinfunction "~{IRQ1}_54") (pintype "bidirectional"))
      (node (ref "2") (pin "54") (pinfunction "~{IRQ1}_54") (pintype "bidirectional"))
      (node (ref "3") (pin "54") (pinfunction "~{IRQ1}_54") (pintype "bidirectional"))
      (node (ref "4") (pin "54") (pinfunction "~{IRQ1}_54") (pintype "bidirectional"))
      (node (ref "5") (pin "54") (pinfunction "~{IRQ1}_54") (pintype "bidirectional"))
      (node (ref "6") (pin "54") (pinfunction "~{IRQ1}_54") (pintype "bidirectional"))
      (node (ref "7") (pin "54") (pinfunction "~{IRQ1}_54") (pintype "bidirectional"))
      (node (ref "RN12") (pin "5") (pinfunction "5_5") (pintype "passive"))
      (node (ref "RN6") (pin "5") (pinfunction "5_5") (pintype "passive"))
    )
    (net (code "115") (name "~{IRQ2}") (class "Default")
      (node (ref "0") (pin "55") (pinfunction "~{IRQ2}_55") (pintype "bidirectional"))
      (node (ref "1") (pin "55") (pinfunction "~{IRQ2}_55") (pintype "bidirectional"))
      (node (ref "2") (pin "52") (pinfunction "~{IRQX}_52") (pintype "bidirectional"))
      (node (ref "2") (pin "55") (pinfunction "~{IRQ2}_55") (pintype "bidirectional"))
      (node (ref "3") (pin "55") (pinfunction "~{IRQ2}_55") (pintype "bidirectional"))
      (node (ref "4") (pin "55") (pinfunction "~{IRQ2}_55") (pintype "bidirectional"))
      (node (ref "5") (pin "55") (pinfunction "~{IRQ2}_55") (pintype "bidirectional"))
      (node (ref "6") (pin "55") (pinfunction "~{IRQ2}_55") (pintype "bidirectional"))
      (node (ref "7") (pin "55") (pinfunction "~{IRQ2}_55") (pintype "bidirectional"))
      (node (ref "RN3") (pin "5") (pinfunction "5_5") (pintype "passive"))
      (node (ref "RN9") (pin "5") (pinfunction "5_5") (pintype "passive"))
    )
    (net (code "116") (name "~{IRQ3}") (class "Default")
      (node (ref "0") (pin "56") (pinfunction "~{IRQ3}_56") (pintype "bidirectional"))
      (node (ref "1") (pin "56") (pinfunction "~{IRQ3}_56") (pintype "bidirectional"))
      (node (ref "2") (pin "56") (pinfunction "~{IRQ3}_56") (pintype "bidirectional"))
      (node (ref "3") (pin "52") (pinfunction "~{IRQX}_52") (pintype "bidirectional"))
      (node (ref "3") (pin "56") (pinfunction "~{IRQ3}_56") (pintype "bidirectional"))
      (node (ref "4") (pin "56") (pinfunction "~{IRQ3}_56") (pintype "bidirectional"))
      (node (ref "5") (pin "56") (pinfunction "~{IRQ3}_56") (pintype "bidirectional"))
      (node (ref "6") (pin "56") (pinfunction "~{IRQ3}_56") (pintype "bidirectional"))
      (node (ref "7") (pin "56") (pinfunction "~{IRQ3}_56") (pintype "bidirectional"))
      (node (ref "RN12") (pin "4") (pinfunction "4_4") (pintype "passive"))
      (node (ref "RN6") (pin "4") (pinfunction "4_4") (pintype "passive"))
    )
    (net (code "117") (name "~{IRQ4}") (class "Default")
      (node (ref "0") (pin "57") (pinfunction "~{IRQ4}_57") (pintype "bidirectional"))
      (node (ref "1") (pin "57") (pinfunction "~{IRQ4}_57") (pintype "bidirectional"))
      (node (ref "2") (pin "57") (pinfunction "~{IRQ4}_57") (pintype "bidirectional"))
      (node (ref "3") (pin "57") (pinfunction "~{IRQ4}_57") (pintype "bidirectional"))
      (node (ref "4") (pin "52") (pinfunction "~{IRQX}_52") (pintype "bidirectional"))
      (node (ref "4") (pin "57") (pinfunction "~{IRQ4}_57") (pintype "bidirectional"))
      (node (ref "5") (pin "57") (pinfunction "~{IRQ4}_57") (pintype "bidirectional"))
      (node (ref "6") (pin "57") (pinfunction "~{IRQ4}_57") (pintype "bidirectional"))
      (node (ref "7") (pin "57") (pinfunction "~{IRQ4}_57") (pintype "bidirectional"))
      (node (ref "RN3") (pin "4") (pinfunction "4_4") (pintype "passive"))
      (node (ref "RN9") (pin "4") (pinfunction "4_4") (pintype "passive"))
    )
    (net (code "118") (name "~{IRQ5}") (class "Default")
      (node (ref "0") (pin "58") (pinfunction "~{IRQ5}_58") (pintype "bidirectional"))
      (node (ref "1") (pin "58") (pinfunction "~{IRQ5}_58") (pintype "bidirectional"))
      (node (ref "2") (pin "58") (pinfunction "~{IRQ5}_58") (pintype "bidirectional"))
      (node (ref "3") (pin "58") (pinfunction "~{IRQ5}_58") (pintype "bidirectional"))
      (node (ref "4") (pin "58") (pinfunction "~{IRQ5}_58") (pintype "bidirectional"))
      (node (ref "5") (pin "52") (pinfunction "~{IRQX}_52") (pintype "bidirectional"))
      (node (ref "5") (pin "58") (pinfunction "~{IRQ5}_58") (pintype "bidirectional"))
      (node (ref "6") (pin "58") (pinfunction "~{IRQ5}_58") (pintype "bidirectional"))
      (node (ref "7") (pin "58") (pinfunction "~{IRQ5}_58") (pintype "bidirectional"))
      (node (ref "RN12") (pin "3") (pinfunction "3_3") (pintype "passive"))
      (node (ref "RN6") (pin "3") (pinfunction "3_3") (pintype "passive"))
    )
    (net (code "119") (name "~{IRQ6}") (class "Default")
      (node (ref "0") (pin "59") (pinfunction "~{IRQ6}_59") (pintype "bidirectional"))
      (node (ref "1") (pin "59") (pinfunction "~{IRQ6}_59") (pintype "bidirectional"))
      (node (ref "2") (pin "59") (pinfunction "~{IRQ6}_59") (pintype "bidirectional"))
      (node (ref "3") (pin "59") (pinfunction "~{IRQ6}_59") (pintype "bidirectional"))
      (node (ref "4") (pin "59") (pinfunction "~{IRQ6}_59") (pintype "bidirectional"))
      (node (ref "5") (pin "59") (pinfunction "~{IRQ6}_59") (pintype "bidirectional"))
      (node (ref "6") (pin "52") (pinfunction "~{IRQX}_52") (pintype "bidirectional"))
      (node (ref "6") (pin "59") (pinfunction "~{IRQ6}_59") (pintype "bidirectional"))
      (node (ref "7") (pin "59") (pinfunction "~{IRQ6}_59") (pintype "bidirectional"))
      (node (ref "RN3") (pin "3") (pinfunction "3_3") (pintype "passive"))
      (node (ref "RN9") (pin "3") (pinfunction "3_3") (pintype "passive"))
    )
    (net (code "120") (name "~{IRQ7}") (class "Default")
      (node (ref "0") (pin "60") (pinfunction "~{IRQ7}_60") (pintype "bidirectional"))
      (node (ref "1") (pin "60") (pinfunction "~{IRQ7}_60") (pintype "bidirectional"))
      (node (ref "2") (pin "60") (pinfunction "~{IRQ7}_60") (pintype "bidirectional"))
      (node (ref "3") (pin "60") (pinfunction "~{IRQ7}_60") (pintype "bidirectional"))
      (node (ref "4") (pin "60") (pinfunction "~{IRQ7}_60") (pintype "bidirectional"))
      (node (ref "5") (pin "60") (pinfunction "~{IRQ7}_60") (pintype "bidirectional"))
      (node (ref "6") (pin "60") (pinfunction "~{IRQ7}_60") (pintype "bidirectional"))
      (node (ref "7") (pin "52") (pinfunction "~{IRQX}_52") (pintype "bidirectional"))
      (node (ref "7") (pin "60") (pinfunction "~{IRQ7}_60") (pintype "bidirectional"))
      (node (ref "RN12") (pin "2") (pinfunction "2_2") (pintype "passive"))
      (node (ref "RN6") (pin "2") (pinfunction "2_2") (pintype "passive"))
    )
    (net (code "121") (name "~{NMI}") (class "Default")
      (node (ref "0") (pin "61") (pinfunction "~{NMI}_61") (pintype "bidirectional"))
      (node (ref "1") (pin "61") (pinfunction "~{NMI}_61") (pintype "bidirectional"))
      (node (ref "2") (pin "61") (pinfunction "~{NMI}_61") (pintype "bidirectional"))
      (node (ref "3") (pin "61") (pinfunction "~{NMI}_61") (pintype "bidirectional"))
      (node (ref "4") (pin "61") (pinfunction "~{NMI}_61") (pintype "bidirectional"))
      (node (ref "5") (pin "61") (pinfunction "~{NMI}_61") (pintype "bidirectional"))
      (node (ref "6") (pin "61") (pinfunction "~{NMI}_61") (pintype "bidirectional"))
      (node (ref "7") (pin "61") (pinfunction "~{NMI}_61") (pintype "bidirectional"))
      (node (ref "RN3") (pin "2") (pinfunction "2_2") (pintype "passive"))
      (node (ref "RN9") (pin "2") (pinfunction "2_2") (pintype "passive"))
    )
    (net (code "122") (name "~{RD}") (class "Default")
      (node (ref "0") (pin "21") (pinfunction "~{RD}_21") (pintype "bidirectional"))
      (node (ref "1") (pin "21") (pinfunction "~{RD}_21") (pintype "bidirectional"))
      (node (ref "2") (pin "21") (pinfunction "~{RD}_21") (pintype "bidirectional"))
      (node (ref "3") (pin "21") (pinfunction "~{RD}_21") (pintype "bidirectional"))
      (node (ref "4") (pin "21") (pinfunction "~{RD}_21") (pintype "bidirectional"))
      (node (ref "5") (pin "21") (pinfunction "~{RD}_21") (pintype "bidirectional"))
      (node (ref "6") (pin "21") (pinfunction "~{RD}_21") (pintype "bidirectional"))
      (node (ref "7") (pin "21") (pinfunction "~{RD}_21") (pintype "bidirectional"))
      (node (ref "RN10") (pin "6") (pinfunction "6_6") (pintype "passive"))
      (node (ref "RN4") (pin "6") (pinfunction "6_6") (pintype "passive"))
    )
    (net (code "123") (name "~{RST}") (class "Default")
      (node (ref "0") (pin "14") (pinfunction "~{RST}_14") (pintype "bidirectional"))
      (node (ref "1") (pin "14") (pinfunction "~{RST}_14") (pintype "bidirectional"))
      (node (ref "2") (pin "14") (pinfunction "~{RST}_14") (pintype "bidirectional"))
      (node (ref "3") (pin "14") (pinfunction "~{RST}_14") (pintype "bidirectional"))
      (node (ref "4") (pin "14") (pinfunction "~{RST}_14") (pintype "bidirectional"))
      (node (ref "5") (pin "14") (pinfunction "~{RST}_14") (pintype "bidirectional"))
      (node (ref "6") (pin "14") (pinfunction "~{RST}_14") (pintype "bidirectional"))
      (node (ref "7") (pin "14") (pinfunction "~{RST}_14") (pintype "bidirectional"))
      (node (ref "JP7") (pin "2") (pinfunction "2_2") (pintype "passive"))
      (node (ref "R10") (pin "1") (pinfunction "1_1") (pintype "passive"))
      (node (ref "RN1") (pin "2") (pinfunction "2_2") (pintype "passive"))
      (node (ref "RN7") (pin "2") (pinfunction "2_2") (pintype "passive"))
    )
    (net (code "124") (name "~{WAIT}") (class "Default")
      (node (ref "0") (pin "18") (pinfunction "~{WAIT}_18") (pintype "bidirectional"))
      (node (ref "1") (pin "18") (pinfunction "~{WAIT}_18") (pintype "bidirectional"))
      (node (ref "2") (pin "18") (pinfunction "~{WAIT}_18") (pintype "bidirectional"))
      (node (ref "3") (pin "18") (pinfunction "~{WAIT}_18") (pintype "bidirectional"))
      (node (ref "4") (pin "18") (pinfunction "~{WAIT}_18") (pintype "bidirectional"))
      (node (ref "5") (pin "18") (pinfunction "~{WAIT}_18") (pintype "bidirectional"))
      (node (ref "6") (pin "18") (pinfunction "~{WAIT}_18") (pintype "bidirectional"))
      (node (ref "7") (pin "18") (pinfunction "~{WAIT}_18") (pintype "bidirectional"))
      (node (ref "RN1") (pin "4") (pinfunction "4_4") (pintype "passive"))
      (node (ref "RN7") (pin "4") (pinfunction "4_4") (pintype "passive"))
    )
    (net (code "125") (name "~{WR}") (class "Default")
      (node (ref "0") (pin "22") (pinfunction "~{WR}_22") (pintype "bidirectional"))
      (node (ref "1") (pin "22") (pinfunction "~{WR}_22") (pintype "bidirectional"))
      (node (ref "2") (pin "22") (pinfunction "~{WR}_22") (pintype "bidirectional"))
      (node (ref "3") (pin "22") (pinfunction "~{WR}_22") (pintype "bidirectional"))
      (node (ref "4") (pin "22") (pinfunction "~{WR}_22") (pintype "bidirectional"))
      (node (ref "5") (pin "22") (pinfunction "~{WR}_22") (pintype "bidirectional"))
      (node (ref "6") (pin "22") (pinfunction "~{WR}_22") (pintype "bidirectional"))
      (node (ref "7") (pin "22") (pinfunction "~{WR}_22") (pintype "bidirectional"))
      (node (ref "RN1") (pin "6") (pinfunction "6_6") (pintype "passive"))
      (node (ref "RN7") (pin "6") (pinfunction "6_6") (pintype "passive"))
    )
  )
)
